# SM3320-BATT-EV.net
KiCad netlist of a schematic drawn in Altium Designer
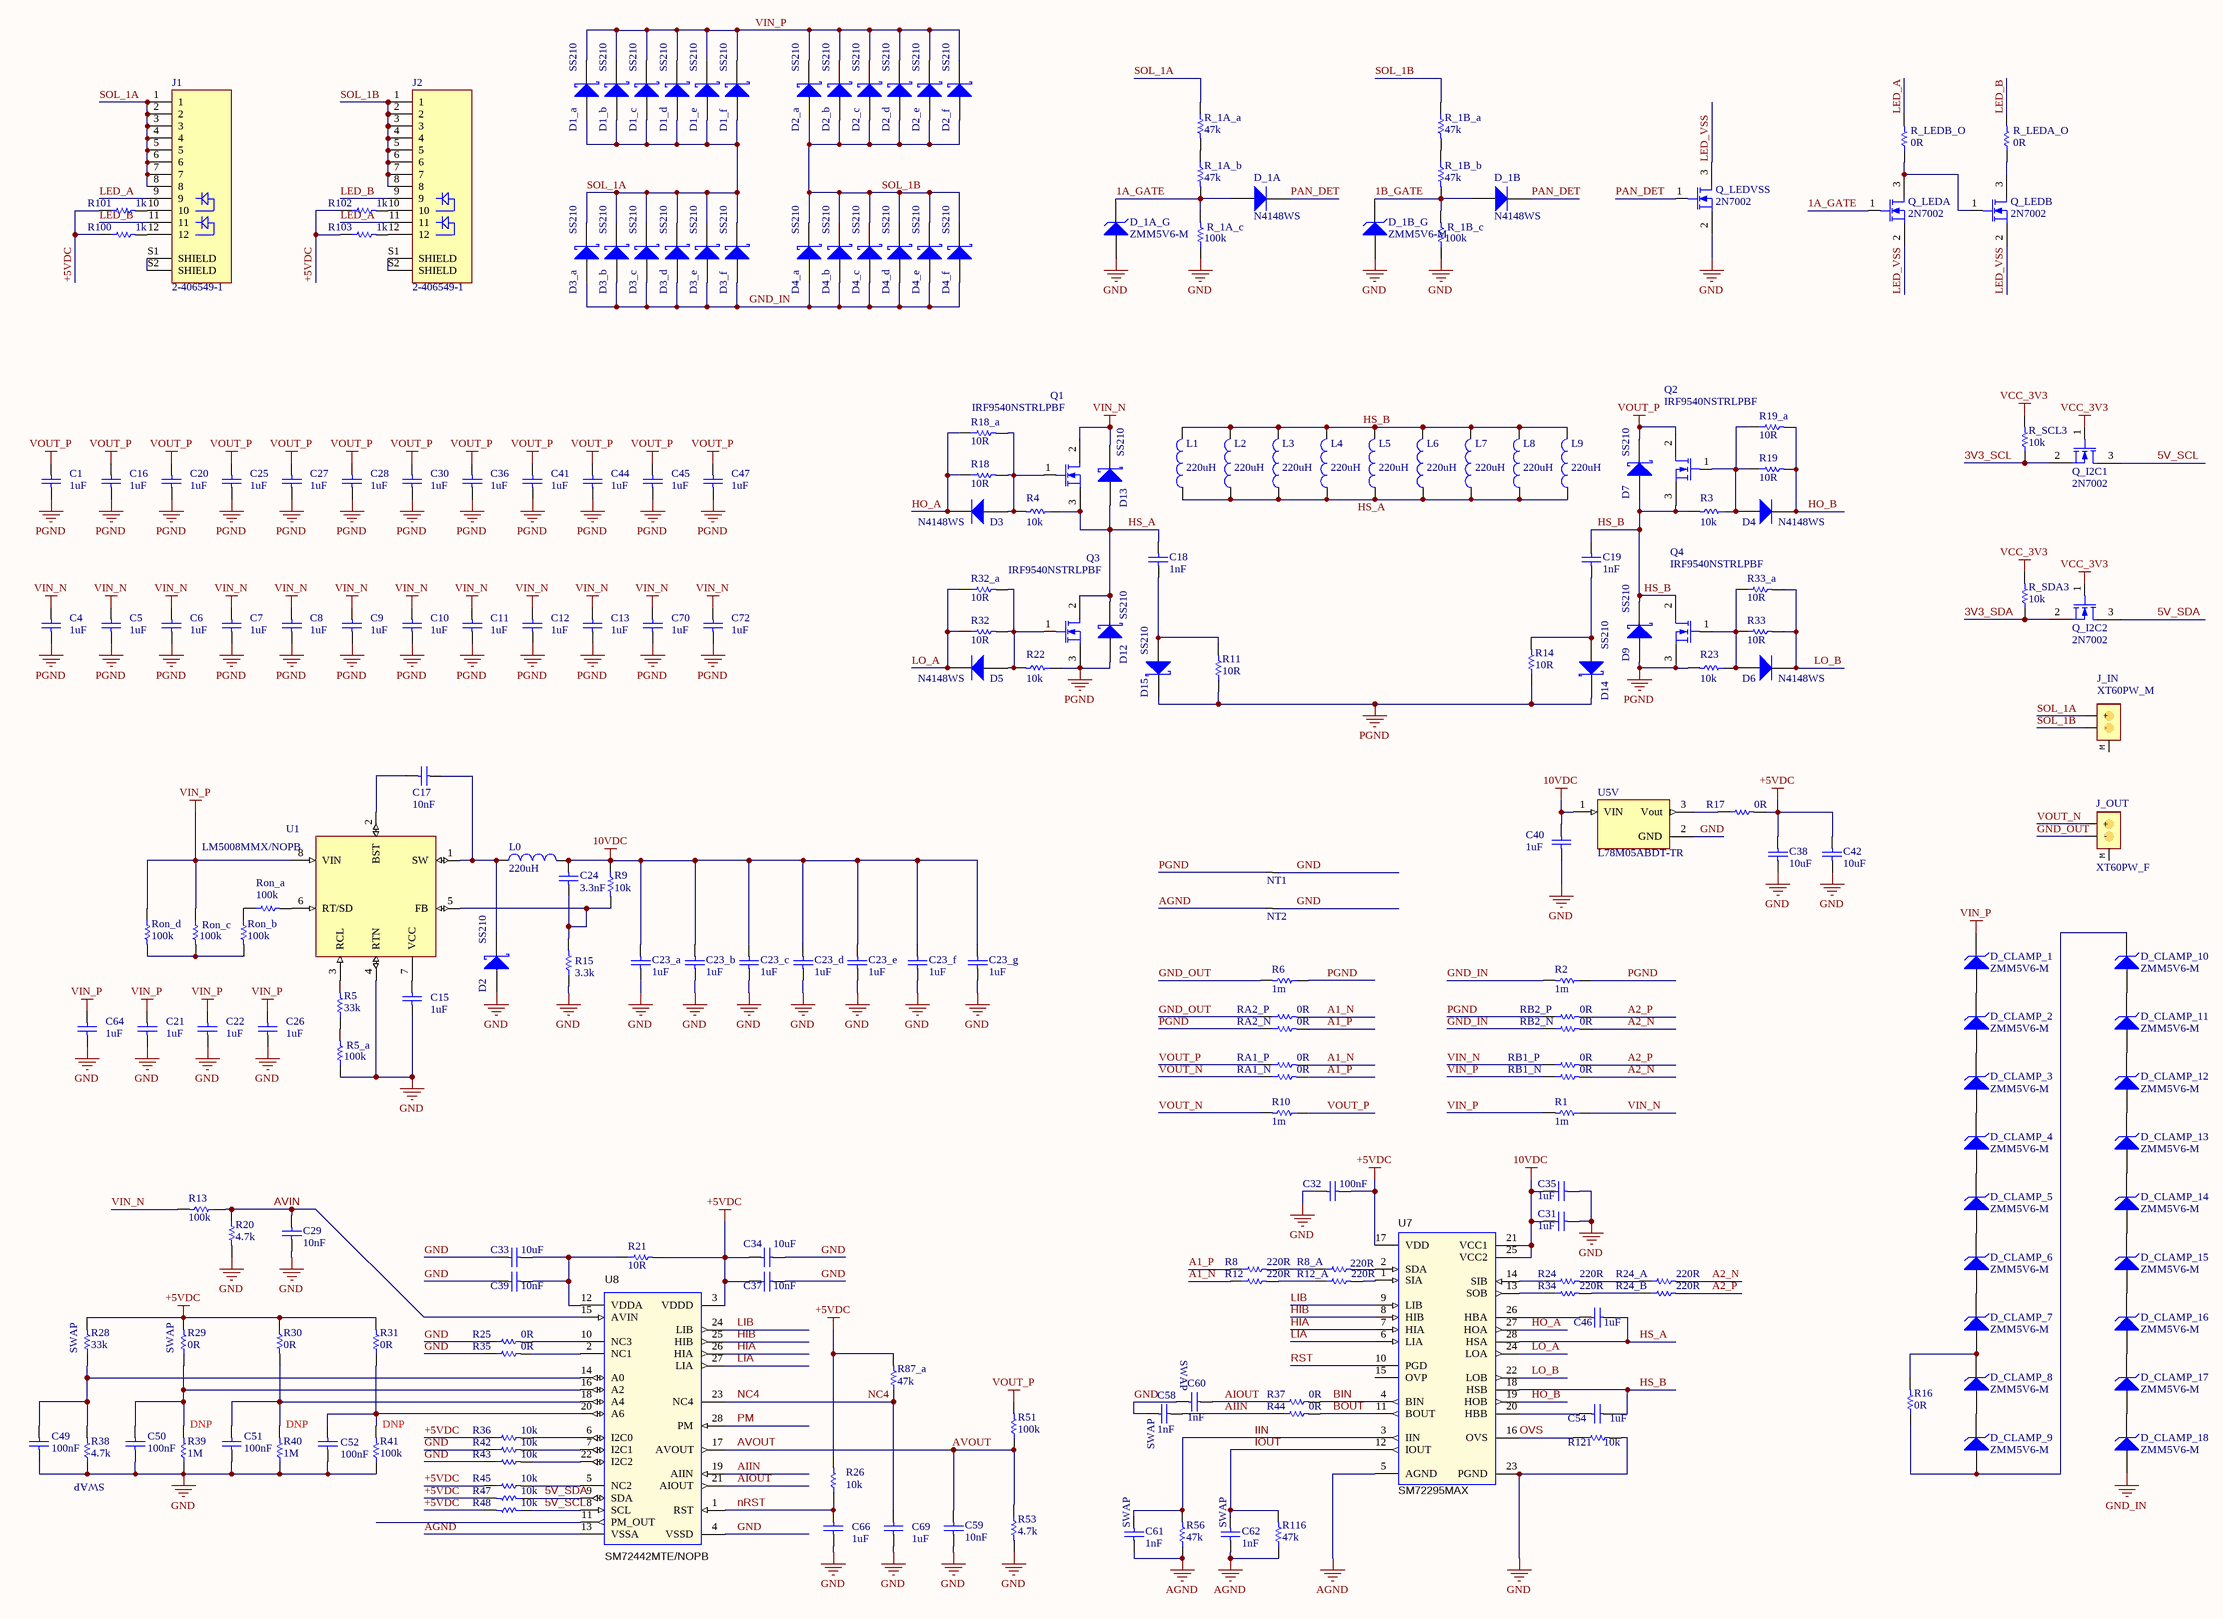
[diagram p0: SM3320-BATT-EV.SchDoc]

(export (version "E")
  (design (tool "Eeschema 10.0.6"))
  (components
    (comp (ref "C1")
      (value "1uF")
      (footprint "C_1206")
      (description "C - CAPACITOR - MLCC - 1uF - 100V - 1206 - X7R")
      (fields (field (name "LCSC PART #") "C91151") (field (name "Comment") "1206B105K101NT"))
      (libsource (lib "JLC_PCB") (part "1206B105K101NT"))
    )
    (comp (ref "C4")
      (value "1uF")
      (footprint "C_1206")
      (description "C - CAPACITOR - MLCC - 1uF - 100V - 1206 - X7R")
      (fields (field (name "LCSC PART #") "C91151") (field (name "Comment") "1206B105K101NT"))
      (libsource (lib "JLC_PCB") (part "1206B105K101NT"))
    )
    (comp (ref "C5")
      (value "1uF")
      (footprint "C_1206")
      (description "C - CAPACITOR - MLCC - 1uF - 100V - 1206 - X7R")
      (fields (field (name "LCSC PART #") "C91151") (field (name "Comment") "1206B105K101NT"))
      (libsource (lib "JLC_PCB") (part "1206B105K101NT"))
    )
    (comp (ref "C6")
      (value "1uF")
      (footprint "C_1206")
      (description "C - CAPACITOR - MLCC - 1uF - 100V - 1206 - X7R")
      (fields (field (name "LCSC PART #") "C91151") (field (name "Comment") "1206B105K101NT"))
      (libsource (lib "JLC_PCB") (part "1206B105K101NT"))
    )
    (comp (ref "C7")
      (value "1uF")
      (footprint "C_1206")
      (description "C - CAPACITOR - MLCC - 1uF - 100V - 1206 - X7R")
      (fields (field (name "LCSC PART #") "C91151") (field (name "Comment") "1206B105K101NT"))
      (libsource (lib "JLC_PCB") (part "1206B105K101NT"))
    )
    (comp (ref "C8")
      (value "1uF")
      (footprint "C_1206")
      (description "C - CAPACITOR - MLCC - 1uF - 100V - 1206 - X7R")
      (fields (field (name "LCSC PART #") "C91151") (field (name "Comment") "1206B105K101NT"))
      (libsource (lib "JLC_PCB") (part "1206B105K101NT"))
    )
    (comp (ref "C9")
      (value "1uF")
      (footprint "C_1206")
      (description "C - CAPACITOR - MLCC - 1uF - 100V - 1206 - X7R")
      (fields (field (name "LCSC PART #") "C91151") (field (name "Comment") "1206B105K101NT"))
      (libsource (lib "JLC_PCB") (part "1206B105K101NT"))
    )
    (comp (ref "C10")
      (value "1uF")
      (footprint "C_1206")
      (description "C - CAPACITOR - MLCC - 1uF - 100V - 1206 - X7R")
      (fields (field (name "LCSC PART #") "C91151") (field (name "Comment") "1206B105K101NT"))
      (libsource (lib "JLC_PCB") (part "1206B105K101NT"))
    )
    (comp (ref "C11")
      (value "1uF")
      (footprint "C_1206")
      (description "C - CAPACITOR - MLCC - 1uF - 100V - 1206 - X7R")
      (fields (field (name "LCSC PART #") "C91151") (field (name "Comment") "1206B105K101NT"))
      (libsource (lib "JLC_PCB") (part "1206B105K101NT"))
    )
    (comp (ref "C12")
      (value "1uF")
      (footprint "C_1206")
      (description "C - CAPACITOR - MLCC - 1uF - 100V - 1206 - X7R")
      (fields (field (name "LCSC PART #") "C91151") (field (name "Comment") "1206B105K101NT"))
      (libsource (lib "JLC_PCB") (part "1206B105K101NT"))
    )
    (comp (ref "C13")
      (value "1uF")
      (footprint "C_1206")
      (description "C - CAPACITOR - MLCC - 1uF - 100V - 1206 - X7R")
      (fields (field (name "LCSC PART #") "C91151") (field (name "Comment") "1206B105K101NT"))
      (libsource (lib "JLC_PCB") (part "1206B105K101NT"))
    )
    (comp (ref "C15")
      (value "1uF")
      (footprint "C_0402")
      (description "C - CAPACITOR - MLCC - 1uF - 25V - 0402")
      (fields (field (name "LCSC PART #") "C52923") (field (name "Comment") "CL05A105KA5NQNC"))
      (libsource (lib "JLC_PCB") (part "CL05A105KA5NQNC"))
    )
    (comp (ref "C16")
      (value "1uF")
      (footprint "C_1206")
      (description "C - CAPACITOR - MLCC - 1uF - 100V - 1206 - X7R")
      (fields (field (name "LCSC PART #") "C91151") (field (name "Comment") "1206B105K101NT"))
      (libsource (lib "JLC_PCB") (part "1206B105K101NT"))
    )
    (comp (ref "C17")
      (value "10nF")
      (footprint "C_0402")
      (description "C - CAPACITOR - MLCC - 10nF - 50V - 0402")
      (fields (field (name "LCSC PART #") "C15195") (field (name "Comment") "CL05B103KB5NNNC"))
      (libsource (lib "JLC_PCB") (part "CL05B103KB5NNNC"))
    )
    (comp (ref "C18")
      (value "1nF")
      (footprint "C_1206")
      (description "C - CAPACITOR - MLCC - 1nF - 2000V - 1206 - X7R")
      (fields (field (name "LCSC PART #") "C9196") (field (name "Comment") "1206B102K202NT"))
      (libsource (lib "JLC_PCB") (part "1206B102K202NT"))
    )
    (comp (ref "C19")
      (value "1nF")
      (footprint "C_1206")
      (description "C - CAPACITOR - MLCC - 1nF - 2000V - 1206 - X7R")
      (fields (field (name "LCSC PART #") "C9196") (field (name "Comment") "1206B102K202NT"))
      (libsource (lib "JLC_PCB") (part "1206B102K202NT"))
    )
    (comp (ref "C20")
      (value "1uF")
      (footprint "C_1206")
      (description "C - CAPACITOR - MLCC - 1uF - 100V - 1206 - X7R")
      (fields (field (name "LCSC PART #") "C91151") (field (name "Comment") "1206B105K101NT"))
      (libsource (lib "JLC_PCB") (part "1206B105K101NT"))
    )
    (comp (ref "C21")
      (value "1uF")
      (footprint "C_1206")
      (description "C - CAPACITOR - MLCC - 1uF - 100V - 1206 - X7R")
      (fields (field (name "LCSC PART #") "C91151") (field (name "Comment") "1206B105K101NT"))
      (libsource (lib "JLC_PCB") (part "1206B105K101NT"))
    )
    (comp (ref "C22")
      (value "1uF")
      (footprint "C_1206")
      (description "C - CAPACITOR - MLCC - 1uF - 100V - 1206 - X7R")
      (fields (field (name "LCSC PART #") "C91151") (field (name "Comment") "1206B105K101NT"))
      (libsource (lib "JLC_PCB") (part "1206B105K101NT"))
    )
    (comp (ref "C23_a")
      (value "1uF")
      (footprint "C_0402")
      (description "C - CAPACITOR - MLCC - 1uF - 25V - 0402")
      (fields (field (name "LCSC PART #") "C52923") (field (name "Comment") "CL05A105KA5NQNC"))
      (libsource (lib "JLC_PCB") (part "CL05A105KA5NQNC"))
    )
    (comp (ref "C23_b")
      (value "1uF")
      (footprint "C_0402")
      (description "C - CAPACITOR - MLCC - 1uF - 25V - 0402")
      (fields (field (name "LCSC PART #") "C52923") (field (name "Comment") "CL05A105KA5NQNC"))
      (libsource (lib "JLC_PCB") (part "CL05A105KA5NQNC"))
    )
    (comp (ref "C23_c")
      (value "1uF")
      (footprint "C_0402")
      (description "C - CAPACITOR - MLCC - 1uF - 25V - 0402")
      (fields (field (name "LCSC PART #") "C52923") (field (name "Comment") "CL05A105KA5NQNC"))
      (libsource (lib "JLC_PCB") (part "CL05A105KA5NQNC"))
    )
    (comp (ref "C23_d")
      (value "1uF")
      (footprint "C_0402")
      (description "C - CAPACITOR - MLCC - 1uF - 25V - 0402")
      (fields (field (name "LCSC PART #") "C52923") (field (name "Comment") "CL05A105KA5NQNC"))
      (libsource (lib "JLC_PCB") (part "CL05A105KA5NQNC"))
    )
    (comp (ref "C23_e")
      (value "1uF")
      (footprint "C_0402")
      (description "C - CAPACITOR - MLCC - 1uF - 25V - 0402")
      (fields (field (name "LCSC PART #") "C52923") (field (name "Comment") "CL05A105KA5NQNC"))
      (libsource (lib "JLC_PCB") (part "CL05A105KA5NQNC"))
    )
    (comp (ref "C23_f")
      (value "1uF")
      (footprint "C_0402")
      (description "C - CAPACITOR - MLCC - 1uF - 25V - 0402")
      (fields (field (name "LCSC PART #") "C52923") (field (name "Comment") "CL05A105KA5NQNC"))
      (libsource (lib "JLC_PCB") (part "CL05A105KA5NQNC"))
    )
    (comp (ref "C23_g")
      (value "1uF")
      (footprint "C_0402")
      (description "C - CAPACITOR - MLCC - 1uF - 25V - 0402")
      (fields (field (name "LCSC PART #") "C52923") (field (name "Comment") "CL05A105KA5NQNC"))
      (libsource (lib "JLC_PCB") (part "CL05A105KA5NQNC"))
    )
    (comp (ref "C24")
      (value "3.3nF")
      (footprint "C_0402")
      (description "C - CAPACITOR - MLCC - 3.3nF - 50V - 0402")
      (fields (field (name "LCSC PART #") "C26404") (field (name "Comment") "CL05B332KB5NNNC"))
      (libsource (lib "JLC_PCB") (part "CL05B332KB5NNNC"))
    )
    (comp (ref "C25")
      (value "1uF")
      (footprint "C_1206")
      (description "C - CAPACITOR - MLCC - 1uF - 100V - 1206 - X7R")
      (fields (field (name "LCSC PART #") "C91151") (field (name "Comment") "1206B105K101NT"))
      (libsource (lib "JLC_PCB") (part "1206B105K101NT"))
    )
    (comp (ref "C26")
      (value "1uF")
      (footprint "C_1206")
      (description "C - CAPACITOR - MLCC - 1uF - 100V - 1206 - X7R")
      (fields (field (name "LCSC PART #") "C91151") (field (name "Comment") "1206B105K101NT"))
      (libsource (lib "JLC_PCB") (part "1206B105K101NT"))
    )
    (comp (ref "C27")
      (value "1uF")
      (footprint "C_1206")
      (description "C - CAPACITOR - MLCC - 1uF - 100V - 1206 - X7R")
      (fields (field (name "LCSC PART #") "C91151") (field (name "Comment") "1206B105K101NT"))
      (libsource (lib "JLC_PCB") (part "1206B105K101NT"))
    )
    (comp (ref "C28")
      (value "1uF")
      (footprint "C_1206")
      (description "C - CAPACITOR - MLCC - 1uF - 100V - 1206 - X7R")
      (fields (field (name "LCSC PART #") "C91151") (field (name "Comment") "1206B105K101NT"))
      (libsource (lib "JLC_PCB") (part "1206B105K101NT"))
    )
    (comp (ref "C29")
      (value "10nF")
      (footprint "C_0402")
      (description "C - CAPACITOR - MLCC - 10nF - 50V - 0402")
      (fields (field (name "LCSC PART #") "C15195") (field (name "Comment") "CL05B103KB5NNNC"))
      (libsource (lib "JLC_PCB") (part "CL05B103KB5NNNC"))
    )
    (comp (ref "C30")
      (value "1uF")
      (footprint "C_1206")
      (description "C - CAPACITOR - MLCC - 1uF - 100V - 1206 - X7R")
      (fields (field (name "LCSC PART #") "C91151") (field (name "Comment") "1206B105K101NT"))
      (libsource (lib "JLC_PCB") (part "1206B105K101NT"))
    )
    (comp (ref "C31")
      (value "1uF")
      (footprint "C_0402")
      (description "C - CAPACITOR - MLCC - 1uF - 25V - 0402")
      (fields (field (name "LCSC PART #") "C52923") (field (name "Comment") "CL05A105KA5NQNC"))
      (libsource (lib "JLC_PCB") (part "CL05A105KA5NQNC"))
    )
    (comp (ref "C32")
      (value "100nF")
      (footprint "C_0402")
      (description "C - CAPACITOR - MLCC - 100nF - 16V - 0402")
      (fields (field (name "LCSC PART #") "C1525") (field (name "Comment") "CL05B104KO5NNNC"))
      (libsource (lib "JLC_PCB") (part "CL05B104KO5NNNC"))
    )
    (comp (ref "C33")
      (value "10uF")
      (footprint "C_0402")
      (description "C - CAPACITOR - MLCC - 10uF - 6.3V - 0402")
      (fields (field (name "LCSC PART #") "C15525") (field (name "Comment") "CL05A106MQ5NUNC"))
      (libsource (lib "JLC_PCB") (part "CL05A106MQ5NUNC"))
    )
    (comp (ref "C34")
      (value "10uF")
      (footprint "C_0402")
      (description "C - CAPACITOR - MLCC - 10uF - 6.3V - 0402")
      (fields (field (name "LCSC PART #") "C15525") (field (name "Comment") "CL05A106MQ5NUNC"))
      (libsource (lib "JLC_PCB") (part "CL05A106MQ5NUNC"))
    )
    (comp (ref "C35")
      (value "1uF")
      (footprint "C_0402")
      (description "C - CAPACITOR - MLCC - 1uF - 25V - 0402")
      (fields (field (name "LCSC PART #") "C52923") (field (name "Comment") "CL05A105KA5NQNC"))
      (libsource (lib "JLC_PCB") (part "CL05A105KA5NQNC"))
    )
    (comp (ref "C36")
      (value "1uF")
      (footprint "C_1206")
      (description "C - CAPACITOR - MLCC - 1uF - 100V - 1206 - X7R")
      (fields (field (name "LCSC PART #") "C91151") (field (name "Comment") "1206B105K101NT"))
      (libsource (lib "JLC_PCB") (part "1206B105K101NT"))
    )
    (comp (ref "C37")
      (value "10nF")
      (footprint "C_0402")
      (description "C - CAPACITOR - MLCC - 10nF - 50V - 0402")
      (fields (field (name "LCSC PART #") "C15195") (field (name "Comment") "CL05B103KB5NNNC"))
      (libsource (lib "JLC_PCB") (part "CL05B103KB5NNNC"))
    )
    (comp (ref "C38")
      (value "10uF")
      (footprint "C_0402")
      (description "C - CAPACITOR - MLCC - 10uF - 6.3V - 0402")
      (fields (field (name "LCSC PART #") "C15525") (field (name "Comment") "CL05A106MQ5NUNC"))
      (libsource (lib "JLC_PCB") (part "CL05A106MQ5NUNC"))
    )
    (comp (ref "C39")
      (value "10nF")
      (footprint "C_0402")
      (description "C - CAPACITOR - MLCC - 10nF - 50V - 0402")
      (fields (field (name "LCSC PART #") "C15195") (field (name "Comment") "CL05B103KB5NNNC"))
      (libsource (lib "JLC_PCB") (part "CL05B103KB5NNNC"))
    )
    (comp (ref "C40")
      (value "1uF")
      (footprint "C_0402")
      (description "C - CAPACITOR - MLCC - 1uF - 25V - 0402")
      (fields (field (name "LCSC PART #") "C52923") (field (name "Comment") "CL05A105KA5NQNC"))
      (libsource (lib "JLC_PCB") (part "CL05A105KA5NQNC"))
    )
    (comp (ref "C41")
      (value "1uF")
      (footprint "C_1206")
      (description "C - CAPACITOR - MLCC - 1uF - 100V - 1206 - X7R")
      (fields (field (name "LCSC PART #") "C91151") (field (name "Comment") "1206B105K101NT"))
      (libsource (lib "JLC_PCB") (part "1206B105K101NT"))
    )
    (comp (ref "C42")
      (value "10uF")
      (footprint "C_0402")
      (description "C - CAPACITOR - MLCC - 10uF - 6.3V - 0402")
      (fields (field (name "LCSC PART #") "C15525") (field (name "Comment") "CL05A106MQ5NUNC"))
      (libsource (lib "JLC_PCB") (part "CL05A106MQ5NUNC"))
    )
    (comp (ref "C44")
      (value "1uF")
      (footprint "C_1206")
      (description "C - CAPACITOR - MLCC - 1uF - 100V - 1206 - X7R")
      (fields (field (name "LCSC PART #") "C91151") (field (name "Comment") "1206B105K101NT"))
      (libsource (lib "JLC_PCB") (part "1206B105K101NT"))
    )
    (comp (ref "C45")
      (value "1uF")
      (footprint "C_1206")
      (description "C - CAPACITOR - MLCC - 1uF - 100V - 1206 - X7R")
      (fields (field (name "LCSC PART #") "C91151") (field (name "Comment") "1206B105K101NT"))
      (libsource (lib "JLC_PCB") (part "1206B105K101NT"))
    )
    (comp (ref "C46")
      (value "1uF")
      (footprint "C_0402")
      (description "C - CAPACITOR - MLCC - 1uF - 25V - 0402")
      (fields (field (name "LCSC PART #") "C52923") (field (name "Comment") "CL05A105KA5NQNC"))
      (libsource (lib "JLC_PCB") (part "CL05A105KA5NQNC"))
    )
    (comp (ref "C47")
      (value "1uF")
      (footprint "C_1206")
      (description "C - CAPACITOR - MLCC - 1uF - 100V - 1206 - X7R")
      (fields (field (name "LCSC PART #") "C91151") (field (name "Comment") "1206B105K101NT"))
      (libsource (lib "JLC_PCB") (part "1206B105K101NT"))
    )
    (comp (ref "C49")
      (value "100nF")
      (footprint "C_0402")
      (description "C - CAPACITOR - MLCC - 100nF - 16V - 0402")
      (fields (field (name "LCSC PART #") "C1525") (field (name "Comment") "CL05B104KO5NNNC"))
      (libsource (lib "JLC_PCB") (part "CL05B104KO5NNNC"))
    )
    (comp (ref "C50")
      (value "100nF")
      (footprint "C_0402")
      (description "C - CAPACITOR - MLCC - 100nF - 16V - 0402")
      (fields (field (name "LCSC PART #") "C1525") (field (name "Comment") "CL05B104KO5NNNC"))
      (libsource (lib "JLC_PCB") (part "CL05B104KO5NNNC"))
    )
    (comp (ref "C51")
      (value "100nF")
      (footprint "C_0402")
      (description "C - CAPACITOR - MLCC - 100nF - 16V - 0402")
      (fields (field (name "LCSC PART #") "C1525") (field (name "Comment") "CL05B104KO5NNNC"))
      (libsource (lib "JLC_PCB") (part "CL05B104KO5NNNC"))
    )
    (comp (ref "C52")
      (value "100nF")
      (footprint "C_0402")
      (description "C - CAPACITOR - MLCC - 100nF - 16V - 0402")
      (fields (field (name "LCSC PART #") "C1525") (field (name "Comment") "CL05B104KO5NNNC"))
      (libsource (lib "JLC_PCB") (part "CL05B104KO5NNNC"))
    )
    (comp (ref "C54")
      (value "1uF")
      (footprint "C_0402")
      (description "C - CAPACITOR - MLCC - 1uF - 25V - 0402")
      (fields (field (name "LCSC PART #") "C52923") (field (name "Comment") "CL05A105KA5NQNC"))
      (libsource (lib "JLC_PCB") (part "CL05A105KA5NQNC"))
    )
    (comp (ref "C58")
      (value "1nF")
      (footprint "C_0402")
      (description "C - CAPACITOR - MLCC - 1nF - 50V - 0402")
      (fields (field (name "LCSC PART #") "C1523") (field (name "Comment") "0402B102K500NT"))
      (libsource (lib "JLC_PCB") (part "0402B102K500NT"))
    )
    (comp (ref "C59")
      (value "10nF")
      (footprint "C_0402")
      (description "C - CAPACITOR - MLCC - 10nF - 50V - 0402")
      (fields (field (name "LCSC PART #") "C15195") (field (name "Comment") "CL05B103KB5NNNC"))
      (libsource (lib "JLC_PCB") (part "CL05B103KB5NNNC"))
    )
    (comp (ref "C60")
      (value "1nF")
      (footprint "C_0402")
      (description "C - CAPACITOR - MLCC - 1nF - 50V - 0402")
      (fields (field (name "LCSC PART #") "C1523") (field (name "Comment") "0402B102K500NT"))
      (libsource (lib "JLC_PCB") (part "0402B102K500NT"))
    )
    (comp (ref "C61")
      (value "1nF")
      (footprint "C_0402")
      (description "C - CAPACITOR - MLCC - 1nF - 50V - 0402")
      (fields (field (name "LCSC PART #") "C1523") (field (name "Comment") "0402B102K500NT"))
      (libsource (lib "JLC_PCB") (part "0402B102K500NT"))
    )
    (comp (ref "C62")
      (value "1nF")
      (footprint "C_0402")
      (description "C - CAPACITOR - MLCC - 1nF - 50V - 0402")
      (fields (field (name "LCSC PART #") "C1523") (field (name "Comment") "0402B102K500NT"))
      (libsource (lib "JLC_PCB") (part "0402B102K500NT"))
    )
    (comp (ref "C64")
      (value "1uF")
      (footprint "C_1206")
      (description "C - CAPACITOR - MLCC - 1uF - 100V - 1206 - X7R")
      (fields (field (name "LCSC PART #") "C91151") (field (name "Comment") "1206B105K101NT"))
      (libsource (lib "JLC_PCB") (part "1206B105K101NT"))
    )
    (comp (ref "C66")
      (value "1uF")
      (footprint "C_0402")
      (description "C - CAPACITOR - MLCC - 1uF - 25V - 0402")
      (fields (field (name "LCSC PART #") "C52923") (field (name "Comment") "CL05A105KA5NQNC"))
      (libsource (lib "JLC_PCB") (part "CL05A105KA5NQNC"))
    )
    (comp (ref "C69")
      (value "1uF")
      (footprint "C_0402")
      (description "C - CAPACITOR - MLCC - 1uF - 25V - 0402")
      (fields (field (name "LCSC PART #") "C52923") (field (name "Comment") "CL05A105KA5NQNC"))
      (libsource (lib "JLC_PCB") (part "CL05A105KA5NQNC"))
    )
    (comp (ref "C70")
      (value "1uF")
      (footprint "C_1206")
      (description "C - CAPACITOR - MLCC - 1uF - 100V - 1206 - X7R")
      (fields (field (name "LCSC PART #") "C91151") (field (name "Comment") "1206B105K101NT"))
      (libsource (lib "JLC_PCB") (part "1206B105K101NT"))
    )
    (comp (ref "C72")
      (value "1uF")
      (footprint "C_1206")
      (description "C - CAPACITOR - MLCC - 1uF - 100V - 1206 - X7R")
      (fields (field (name "LCSC PART #") "C91151") (field (name "Comment") "1206B105K101NT"))
      (libsource (lib "JLC_PCB") (part "1206B105K101NT"))
    )
    (comp (ref "D1_a")
      (value "SS210")
      (footprint "DO-214AC")
      (description "D - DIODE - SCHOTTKY - 100V - 2A")
      (fields (field (name "LCSC PART #") "C14996"))
      (libsource (lib "JLC_PCB") (part "SS210"))
    )
    (comp (ref "D1_b")
      (value "SS210")
      (footprint "DO-214AC")
      (description "D - DIODE - SCHOTTKY - 100V - 2A")
      (fields (field (name "LCSC PART #") "C14996"))
      (libsource (lib "JLC_PCB") (part "SS210"))
    )
    (comp (ref "D1_c")
      (value "SS210")
      (footprint "DO-214AC")
      (description "D - DIODE - SCHOTTKY - 100V - 2A")
      (fields (field (name "LCSC PART #") "C14996"))
      (libsource (lib "JLC_PCB") (part "SS210"))
    )
    (comp (ref "D1_d")
      (value "SS210")
      (footprint "DO-214AC")
      (description "D - DIODE - SCHOTTKY - 100V - 2A")
      (fields (field (name "LCSC PART #") "C14996"))
      (libsource (lib "JLC_PCB") (part "SS210"))
    )
    (comp (ref "D1_e")
      (value "SS210")
      (footprint "DO-214AC")
      (description "D - DIODE - SCHOTTKY - 100V - 2A")
      (fields (field (name "LCSC PART #") "C14996"))
      (libsource (lib "JLC_PCB") (part "SS210"))
    )
    (comp (ref "D1_f")
      (value "SS210")
      (footprint "DO-214AC")
      (description "D - DIODE - SCHOTTKY - 100V - 2A")
      (fields (field (name "LCSC PART #") "C14996"))
      (libsource (lib "JLC_PCB") (part "SS210"))
    )
    (comp (ref "D2")
      (value "SS210")
      (footprint "DO-214AC")
      (description "D - DIODE - SCHOTTKY - 100V - 2A")
      (fields (field (name "LCSC PART #") "C14996"))
      (libsource (lib "JLC_PCB") (part "SS210"))
    )
    (comp (ref "D2_a")
      (value "SS210")
      (footprint "DO-214AC")
      (description "D - DIODE - SCHOTTKY - 100V - 2A")
      (fields (field (name "LCSC PART #") "C14996"))
      (libsource (lib "JLC_PCB") (part "SS210"))
    )
    (comp (ref "D2_b")
      (value "SS210")
      (footprint "DO-214AC")
      (description "D - DIODE - SCHOTTKY - 100V - 2A")
      (fields (field (name "LCSC PART #") "C14996"))
      (libsource (lib "JLC_PCB") (part "SS210"))
    )
    (comp (ref "D2_c")
      (value "SS210")
      (footprint "DO-214AC")
      (description "D - DIODE - SCHOTTKY - 100V - 2A")
      (fields (field (name "LCSC PART #") "C14996"))
      (libsource (lib "JLC_PCB") (part "SS210"))
    )
    (comp (ref "D2_d")
      (value "SS210")
      (footprint "DO-214AC")
      (description "D - DIODE - SCHOTTKY - 100V - 2A")
      (fields (field (name "LCSC PART #") "C14996"))
      (libsource (lib "JLC_PCB") (part "SS210"))
    )
    (comp (ref "D2_e")
      (value "SS210")
      (footprint "DO-214AC")
      (description "D - DIODE - SCHOTTKY - 100V - 2A")
      (fields (field (name "LCSC PART #") "C14996"))
      (libsource (lib "JLC_PCB") (part "SS210"))
    )
    (comp (ref "D2_f")
      (value "SS210")
      (footprint "DO-214AC")
      (description "D - DIODE - SCHOTTKY - 100V - 2A")
      (fields (field (name "LCSC PART #") "C14996"))
      (libsource (lib "JLC_PCB") (part "SS210"))
    )
    (comp (ref "D3")
      (value "N4148WS")
      (footprint "SOD-323")
      (description "D - DIODE - FAST TRR - 100V - 150mA - 4ns")
      (fields (field (name "LCSC PART #") "C2128"))
      (libsource (lib "JLC_PCB") (part "N4148WS"))
    )
    (comp (ref "D3_a")
      (value "SS210")
      (footprint "DO-214AC")
      (description "D - DIODE - SCHOTTKY - 100V - 2A")
      (fields (field (name "LCSC PART #") "C14996"))
      (libsource (lib "JLC_PCB") (part "SS210"))
    )
    (comp (ref "D3_b")
      (value "SS210")
      (footprint "DO-214AC")
      (description "D - DIODE - SCHOTTKY - 100V - 2A")
      (fields (field (name "LCSC PART #") "C14996"))
      (libsource (lib "JLC_PCB") (part "SS210"))
    )
    (comp (ref "D3_c")
      (value "SS210")
      (footprint "DO-214AC")
      (description "D - DIODE - SCHOTTKY - 100V - 2A")
      (fields (field (name "LCSC PART #") "C14996"))
      (libsource (lib "JLC_PCB") (part "SS210"))
    )
    (comp (ref "D3_d")
      (value "SS210")
      (footprint "DO-214AC")
      (description "D - DIODE - SCHOTTKY - 100V - 2A")
      (fields (field (name "LCSC PART #") "C14996"))
      (libsource (lib "JLC_PCB") (part "SS210"))
    )
    (comp (ref "D3_e")
      (value "SS210")
      (footprint "DO-214AC")
      (description "D - DIODE - SCHOTTKY - 100V - 2A")
      (fields (field (name "LCSC PART #") "C14996"))
      (libsource (lib "JLC_PCB") (part "SS210"))
    )
    (comp (ref "D3_f")
      (value "SS210")
      (footprint "DO-214AC")
      (description "D - DIODE - SCHOTTKY - 100V - 2A")
      (fields (field (name "LCSC PART #") "C14996"))
      (libsource (lib "JLC_PCB") (part "SS210"))
    )
    (comp (ref "D4")
      (value "N4148WS")
      (footprint "SOD-323")
      (description "D - DIODE - FAST TRR - 100V - 150mA - 4ns")
      (fields (field (name "LCSC PART #") "C2128"))
      (libsource (lib "JLC_PCB") (part "N4148WS"))
    )
    (comp (ref "D4_a")
      (value "SS210")
      (footprint "DO-214AC")
      (description "D - DIODE - SCHOTTKY - 100V - 2A")
      (fields (field (name "LCSC PART #") "C14996"))
      (libsource (lib "JLC_PCB") (part "SS210"))
    )
    (comp (ref "D4_b")
      (value "SS210")
      (footprint "DO-214AC")
      (description "D - DIODE - SCHOTTKY - 100V - 2A")
      (fields (field (name "LCSC PART #") "C14996"))
      (libsource (lib "JLC_PCB") (part "SS210"))
    )
    (comp (ref "D4_c")
      (value "SS210")
      (footprint "DO-214AC")
      (description "D - DIODE - SCHOTTKY - 100V - 2A")
      (fields (field (name "LCSC PART #") "C14996"))
      (libsource (lib "JLC_PCB") (part "SS210"))
    )
    (comp (ref "D4_d")
      (value "SS210")
      (footprint "DO-214AC")
      (description "D - DIODE - SCHOTTKY - 100V - 2A")
      (fields (field (name "LCSC PART #") "C14996"))
      (libsource (lib "JLC_PCB") (part "SS210"))
    )
    (comp (ref "D4_e")
      (value "SS210")
      (footprint "DO-214AC")
      (description "D - DIODE - SCHOTTKY - 100V - 2A")
      (fields (field (name "LCSC PART #") "C14996"))
      (libsource (lib "JLC_PCB") (part "SS210"))
    )
    (comp (ref "D4_f")
      (value "SS210")
      (footprint "DO-214AC")
      (description "D - DIODE - SCHOTTKY - 100V - 2A")
      (fields (field (name "LCSC PART #") "C14996"))
      (libsource (lib "JLC_PCB") (part "SS210"))
    )
    (comp (ref "D5")
      (value "N4148WS")
      (footprint "SOD-323")
      (description "D - DIODE - FAST TRR - 100V - 150mA - 4ns")
      (fields (field (name "LCSC PART #") "C2128"))
      (libsource (lib "JLC_PCB") (part "N4148WS"))
    )
    (comp (ref "D6")
      (value "N4148WS")
      (footprint "SOD-323")
      (description "D - DIODE - FAST TRR - 100V - 150mA - 4ns")
      (fields (field (name "LCSC PART #") "C2128"))
      (libsource (lib "JLC_PCB") (part "N4148WS"))
    )
    (comp (ref "D7")
      (value "SS210")
      (footprint "DO-214AC")
      (description "D - DIODE - SCHOTTKY - 100V - 2A")
      (fields (field (name "LCSC PART #") "C14996"))
      (libsource (lib "JLC_PCB") (part "SS210"))
    )
    (comp (ref "D9")
      (value "SS210")
      (footprint "DO-214AC")
      (description "D - DIODE - SCHOTTKY - 100V - 2A")
      (fields (field (name "LCSC PART #") "C14996"))
      (libsource (lib "JLC_PCB") (part "SS210"))
    )
    (comp (ref "D12")
      (value "SS210")
      (footprint "DO-214AC")
      (description "D - DIODE - SCHOTTKY - 100V - 2A")
      (fields (field (name "LCSC PART #") "C14996"))
      (libsource (lib "JLC_PCB") (part "SS210"))
    )
    (comp (ref "D13")
      (value "SS210")
      (footprint "DO-214AC")
      (description "D - DIODE - SCHOTTKY - 100V - 2A")
      (fields (field (name "LCSC PART #") "C14996"))
      (libsource (lib "JLC_PCB") (part "SS210"))
    )
    (comp (ref "D14")
      (value "SS210")
      (footprint "DO-214AC")
      (description "D - DIODE - SCHOTTKY - 100V - 2A")
      (fields (field (name "LCSC PART #") "C14996"))
      (libsource (lib "JLC_PCB") (part "SS210"))
    )
    (comp (ref "D15")
      (value "SS210")
      (footprint "DO-214AC")
      (description "D - DIODE - SCHOTTKY - 100V - 2A")
      (fields (field (name "LCSC PART #") "C14996"))
      (libsource (lib "JLC_PCB") (part "SS210"))
    )
    (comp (ref "D_1A")
      (value "N4148WS")
      (footprint "SOD-323")
      (description "D - DIODE - FAST TRR - 100V - 150mA - 4ns")
      (fields (field (name "LCSC PART #") "C2128"))
      (libsource (lib "JLC_PCB") (part "N4148WS"))
    )
    (comp (ref "D_1A_G")
      (value "ZMM5V6-M")
      (footprint "DO-213AA")
      (description "D - DIODE - ZENER - 5.6V - 500mW")
      (fields (field (name "LCSC PART #") "C8062"))
      (libsource (lib "JLC_PCB") (part "ZMM5V6-M"))
    )
    (comp (ref "D_1B")
      (value "N4148WS")
      (footprint "SOD-323")
      (description "D - DIODE - FAST TRR - 100V - 150mA - 4ns")
      (fields (field (name "LCSC PART #") "C2128"))
      (libsource (lib "JLC_PCB") (part "N4148WS"))
    )
    (comp (ref "D_1B_G")
      (value "ZMM5V6-M")
      (footprint "DO-213AA")
      (description "D - DIODE - ZENER - 5.6V - 500mW")
      (fields (field (name "LCSC PART #") "C8062"))
      (libsource (lib "JLC_PCB") (part "ZMM5V6-M"))
    )
    (comp (ref "D_CLAMP_1")
      (value "ZMM5V6-M")
      (footprint "DO-213AA")
      (description "D - DIODE - ZENER - 5.6V - 500mW")
      (fields (field (name "LCSC PART #") "C8062"))
      (libsource (lib "JLC_PCB") (part "ZMM5V6-M"))
    )
    (comp (ref "D_CLAMP_2")
      (value "ZMM5V6-M")
      (footprint "DO-213AA")
      (description "D - DIODE - ZENER - 5.6V - 500mW")
      (fields (field (name "LCSC PART #") "C8062"))
      (libsource (lib "JLC_PCB") (part "ZMM5V6-M"))
    )
    (comp (ref "D_CLAMP_3")
      (value "ZMM5V6-M")
      (footprint "DO-213AA")
      (description "D - DIODE - ZENER - 5.6V - 500mW")
      (fields (field (name "LCSC PART #") "C8062"))
      (libsource (lib "JLC_PCB") (part "ZMM5V6-M"))
    )
    (comp (ref "D_CLAMP_4")
      (value "ZMM5V6-M")
      (footprint "DO-213AA")
      (description "D - DIODE - ZENER - 5.6V - 500mW")
      (fields (field (name "LCSC PART #") "C8062"))
      (libsource (lib "JLC_PCB") (part "ZMM5V6-M"))
    )
    (comp (ref "D_CLAMP_5")
      (value "ZMM5V6-M")
      (footprint "DO-213AA")
      (description "D - DIODE - ZENER - 5.6V - 500mW")
      (fields (field (name "LCSC PART #") "C8062"))
      (libsource (lib "JLC_PCB") (part "ZMM5V6-M"))
    )
    (comp (ref "D_CLAMP_6")
      (value "ZMM5V6-M")
      (footprint "DO-213AA")
      (description "D - DIODE - ZENER - 5.6V - 500mW")
      (fields (field (name "LCSC PART #") "C8062"))
      (libsource (lib "JLC_PCB") (part "ZMM5V6-M"))
    )
    (comp (ref "D_CLAMP_7")
      (value "ZMM5V6-M")
      (footprint "DO-213AA")
      (description "D - DIODE - ZENER - 5.6V - 500mW")
      (fields (field (name "LCSC PART #") "C8062"))
      (libsource (lib "JLC_PCB") (part "ZMM5V6-M"))
    )
    (comp (ref "D_CLAMP_8")
      (value "ZMM5V6-M")
      (footprint "DO-213AA")
      (description "D - DIODE - ZENER - 5.6V - 500mW")
      (fields (field (name "LCSC PART #") "C8062"))
      (libsource (lib "JLC_PCB") (part "ZMM5V6-M"))
    )
    (comp (ref "D_CLAMP_9")
      (value "ZMM5V6-M")
      (footprint "DO-213AA")
      (description "D - DIODE - ZENER - 5.6V - 500mW")
      (fields (field (name "LCSC PART #") "C8062"))
      (libsource (lib "JLC_PCB") (part "ZMM5V6-M"))
    )
    (comp (ref "D_CLAMP_10")
      (value "ZMM5V6-M")
      (footprint "DO-213AA")
      (description "D - DIODE - ZENER - 5.6V - 500mW")
      (fields (field (name "LCSC PART #") "C8062"))
      (libsource (lib "JLC_PCB") (part "ZMM5V6-M"))
    )
    (comp (ref "D_CLAMP_11")
      (value "ZMM5V6-M")
      (footprint "DO-213AA")
      (description "D - DIODE - ZENER - 5.6V - 500mW")
      (fields (field (name "LCSC PART #") "C8062"))
      (libsource (lib "JLC_PCB") (part "ZMM5V6-M"))
    )
    (comp (ref "D_CLAMP_12")
      (value "ZMM5V6-M")
      (footprint "DO-213AA")
      (description "D - DIODE - ZENER - 5.6V - 500mW")
      (fields (field (name "LCSC PART #") "C8062"))
      (libsource (lib "JLC_PCB") (part "ZMM5V6-M"))
    )
    (comp (ref "D_CLAMP_13")
      (value "ZMM5V6-M")
      (footprint "DO-213AA")
      (description "D - DIODE - ZENER - 5.6V - 500mW")
      (fields (field (name "LCSC PART #") "C8062"))
      (libsource (lib "JLC_PCB") (part "ZMM5V6-M"))
    )
    (comp (ref "D_CLAMP_14")
      (value "ZMM5V6-M")
      (footprint "DO-213AA")
      (description "D - DIODE - ZENER - 5.6V - 500mW")
      (fields (field (name "LCSC PART #") "C8062"))
      (libsource (lib "JLC_PCB") (part "ZMM5V6-M"))
    )
    (comp (ref "D_CLAMP_15")
      (value "ZMM5V6-M")
      (footprint "DO-213AA")
      (description "D - DIODE - ZENER - 5.6V - 500mW")
      (fields (field (name "LCSC PART #") "C8062"))
      (libsource (lib "JLC_PCB") (part "ZMM5V6-M"))
    )
    (comp (ref "D_CLAMP_16")
      (value "ZMM5V6-M")
      (footprint "DO-213AA")
      (description "D - DIODE - ZENER - 5.6V - 500mW")
      (fields (field (name "LCSC PART #") "C8062"))
      (libsource (lib "JLC_PCB") (part "ZMM5V6-M"))
    )
    (comp (ref "D_CLAMP_17")
      (value "ZMM5V6-M")
      (footprint "DO-213AA")
      (description "D - DIODE - ZENER - 5.6V - 500mW")
      (fields (field (name "LCSC PART #") "C8062"))
      (libsource (lib "JLC_PCB") (part "ZMM5V6-M"))
    )
    (comp (ref "D_CLAMP_18")
      (value "ZMM5V6-M")
      (footprint "DO-213AA")
      (description "D - DIODE - ZENER - 5.6V - 500mW")
      (fields (field (name "LCSC PART #") "C8062"))
      (libsource (lib "JLC_PCB") (part "ZMM5V6-M"))
    )
    (comp (ref "J1")
      (value "2-406549-1")
      (footprint "TE_2-406549-1")
      (description "J - JACK - ETHERNET - Right - THT")
      (fields (field (name "LCSC PART #") "C125068"))
      (libsource (lib "JLC_PCB") (part "2-406549-1"))
    )
    (comp (ref "J2")
      (value "2-406549-1")
      (footprint "TE_2-406549-1")
      (description "J - JACK - ETHERNET - Right - THT")
      (fields (field (name "LCSC PART #") "C125068"))
      (libsource (lib "JLC_PCB") (part "2-406549-1"))
    )
    (comp (ref "J_IN")
      (value "XT60PW_M")
      (footprint "XT60PW_M")
      (description "J - JACK - POWER - XT60 - RIGHT - MALE")
      (fields (field (name "LCSC PART #") "X"))
      (libsource (lib "JLC_PCB") (part "XT60PW_M"))
    )
    (comp (ref "J_OUT")
      (value "XT60PW_F")
      (footprint "XT60PW_F")
      (description "J - JACK - POWER - XT60 - RIGHT - FEMALE")
      (fields (field (name "LCSC PART #") "X"))
      (libsource (lib "JLC_PCB") (part "XT60PW_F"))
    )
    (comp (ref "L0")
      (value "220uH")
      (footprint "SRR1260")
      (description "L - INDUCTOR - 220uH - 1.6A - 12.5mm")
      (fields (field (name "LCSC PART #") "C169380") (field (name "Comment") "SWRB1207S-221MT"))
      (libsource (lib "JLC_PCB") (part "SWRB1207S-221MT"))
    )
    (comp (ref "L1")
      (value "220uH")
      (footprint "SRR1260")
      (description "L - INDUCTOR - 220uH - 1.6A - 12.5mm")
      (fields (field (name "LCSC PART #") "C169380") (field (name "Comment") "SWRB1207S-221MT"))
      (libsource (lib "JLC_PCB") (part "SWRB1207S-221MT"))
    )
    (comp (ref "L2")
      (value "220uH")
      (footprint "SRR1260")
      (description "L - INDUCTOR - 220uH - 1.6A - 12.5mm")
      (fields (field (name "LCSC PART #") "C169380") (field (name "Comment") "SWRB1207S-221MT"))
      (libsource (lib "JLC_PCB") (part "SWRB1207S-221MT"))
    )
    (comp (ref "L3")
      (value "220uH")
      (footprint "SRR1260")
      (description "L - INDUCTOR - 220uH - 1.6A - 12.5mm")
      (fields (field (name "LCSC PART #") "C169380") (field (name "Comment") "SWRB1207S-221MT"))
      (libsource (lib "JLC_PCB") (part "SWRB1207S-221MT"))
    )
    (comp (ref "L4")
      (value "220uH")
      (footprint "SRR1260")
      (description "L - INDUCTOR - 220uH - 1.6A - 12.5mm")
      (fields (field (name "LCSC PART #") "C169380") (field (name "Comment") "SWRB1207S-221MT"))
      (libsource (lib "JLC_PCB") (part "SWRB1207S-221MT"))
    )
    (comp (ref "L5")
      (value "220uH")
      (footprint "SRR1260")
      (description "L - INDUCTOR - 220uH - 1.6A - 12.5mm")
      (fields (field (name "LCSC PART #") "C169380") (field (name "Comment") "SWRB1207S-221MT"))
      (libsource (lib "JLC_PCB") (part "SWRB1207S-221MT"))
    )
    (comp (ref "L6")
      (value "220uH")
      (footprint "SRR1260")
      (description "L - INDUCTOR - 220uH - 1.6A - 12.5mm")
      (fields (field (name "LCSC PART #") "C169380") (field (name "Comment") "SWRB1207S-221MT"))
      (libsource (lib "JLC_PCB") (part "SWRB1207S-221MT"))
    )
    (comp (ref "L7")
      (value "220uH")
      (footprint "SRR1260")
      (description "L - INDUCTOR - 220uH - 1.6A - 12.5mm")
      (fields (field (name "LCSC PART #") "C169380") (field (name "Comment") "SWRB1207S-221MT"))
      (libsource (lib "JLC_PCB") (part "SWRB1207S-221MT"))
    )
    (comp (ref "L8")
      (value "220uH")
      (footprint "SRR1260")
      (description "L - INDUCTOR - 220uH - 1.6A - 12.5mm")
      (fields (field (name "LCSC PART #") "C169380") (field (name "Comment") "SWRB1207S-221MT"))
      (libsource (lib "JLC_PCB") (part "SWRB1207S-221MT"))
    )
    (comp (ref "L9")
      (value "220uH")
      (footprint "SRR1260")
      (description "L - INDUCTOR - 220uH - 1.6A - 12.5mm")
      (fields (field (name "LCSC PART #") "C169380") (field (name "Comment") "SWRB1207S-221MT"))
      (libsource (lib "JLC_PCB") (part "SWRB1207S-221MT"))
    )
    (comp (ref "NT1")
      (value "0")
      (footprint "NET_TIE")
      (description "R - Net Tie")
      (libsource (lib "JLC_PCB") (part "NET_TIE"))
    )
    (comp (ref "NT2")
      (value "0")
      (footprint "NET_TIE")
      (description "R - Net Tie")
      (libsource (lib "JLC_PCB") (part "NET_TIE"))
    )
    (comp (ref "Q1")
      (value "IRF9540NSTRLPBF")
      (footprint "TO-263-3")
      (description "Q - TRANSISTOR - MOSFET (N) - 250V - 33A - 0.094R")
      (fields (field (name "LCSC PART #") "C33903"))
      (libsource (lib "JLC_PCB") (part "IRF9540NSTRLPBF"))
    )
    (comp (ref "Q2")
      (value "IRF9540NSTRLPBF")
      (footprint "TO-263-3")
      (description "Q - TRANSISTOR - MOSFET (N) - 250V - 33A - 0.094R")
      (fields (field (name "LCSC PART #") "C33903"))
      (libsource (lib "JLC_PCB") (part "IRF9540NSTRLPBF"))
    )
    (comp (ref "Q3")
      (value "IRF9540NSTRLPBF")
      (footprint "TO-263-3")
      (description "Q - TRANSISTOR - MOSFET (N) - 250V - 33A - 0.094R")
      (fields (field (name "LCSC PART #") "C33903"))
      (libsource (lib "JLC_PCB") (part "IRF9540NSTRLPBF"))
    )
    (comp (ref "Q4")
      (value "IRF9540NSTRLPBF")
      (footprint "TO-263-3")
      (description "Q - TRANSISTOR - MOSFET (N) - 250V - 33A - 0.094R")
      (fields (field (name "LCSC PART #") "C33903"))
      (libsource (lib "JLC_PCB") (part "IRF9540NSTRLPBF"))
    )
    (comp (ref "Q_I2C1")
      (value "2N7002")
      (footprint "TO-236AB")
      (description "Q - TRANSISTOR - MOSFET (N) - 60V - 200mW")
      (fields (field (name "LCSC PART #") "C8545"))
      (libsource (lib "JLC_PCB") (part "2N7002"))
    )
    (comp (ref "Q_I2C2")
      (value "2N7002")
      (footprint "TO-236AB")
      (description "Q - TRANSISTOR - MOSFET (N) - 60V - 200mW")
      (fields (field (name "LCSC PART #") "C8545"))
      (libsource (lib "JLC_PCB") (part "2N7002"))
    )
    (comp (ref "Q_LEDA")
      (value "2N7002")
      (footprint "TO-236AB")
      (description "Q - TRANSISTOR - MOSFET (N) - 60V - 200mW")
      (fields (field (name "LCSC PART #") "C8545"))
      (libsource (lib "JLC_PCB") (part "2N7002"))
    )
    (comp (ref "Q_LEDB")
      (value "2N7002")
      (footprint "TO-236AB")
      (description "Q - TRANSISTOR - MOSFET (N) - 60V - 200mW")
      (fields (field (name "LCSC PART #") "C8545"))
      (libsource (lib "JLC_PCB") (part "2N7002"))
    )
    (comp (ref "Q_LEDVSS")
      (value "2N7002")
      (footprint "TO-236AB")
      (description "Q - TRANSISTOR - MOSFET (N) - 60V - 200mW")
      (fields (field (name "LCSC PART #") "C8545"))
      (libsource (lib "JLC_PCB") (part "2N7002"))
    )
    (comp (ref "R1")
      (value "1m")
      (footprint "R_2512")
      (description "R - RESISTOR - SMD - 0.001R - 1% - 2512 - 2W - 50ppm/k")
      (fields (field (name "LCSC PART #") "C349153") (field (name "POWER") "2W"))
      (libsource (lib "JLC_PCB") (part "EWSL2512F1L00S9"))
    )
    (comp (ref "R2")
      (value "1m")
      (footprint "R_2512")
      (description "R - RESISTOR - SMD - 0.001R - 1% - 2512 - 2W - 50ppm/k")
      (fields (field (name "LCSC PART #") "C349153") (field (name "POWER") "2W"))
      (libsource (lib "JLC_PCB") (part "EWSL2512F1L00S9"))
    )
    (comp (ref "R3")
      (value "10k")
      (footprint "R_0402")
      (description "R - RESISTOR - SMD - 10k - 1% - 0402")
      (fields (field (name "LCSC PART #") "C25744") (field (name "Comment") "0402WGF1002TCE"))
      (libsource (lib "JLC_PCB") (part "0402WGF1002TCE"))
    )
    (comp (ref "R4")
      (value "10k")
      (footprint "R_0402")
      (description "R - RESISTOR - SMD - 10k - 1% - 0402")
      (fields (field (name "LCSC PART #") "C25744") (field (name "Comment") "0402WGF1002TCE"))
      (libsource (lib "JLC_PCB") (part "0402WGF1002TCE"))
    )
    (comp (ref "R5")
      (value "33k")
      (footprint "R_0402")
      (description "R - RESISTOR - SMD - 33k - 1% - 0402")
      (fields (field (name "LCSC PART #") "C25779") (field (name "Comment") "0402WGF3302TCE"))
      (libsource (lib "JLC_PCB") (part "0402WGF3302TCE"))
    )
    (comp (ref "R5_a")
      (value "100k")
      (footprint "R_0402")
      (description "R - RESISTOR - SMD - 100k - 1% -  0402")
      (fields (field (name "LCSC PART #") "C25741") (field (name "Comment") "0402WGF1003TCE"))
      (libsource (lib "JLC_PCB") (part "0402WGF1003TCE"))
    )
    (comp (ref "R6")
      (value "1m")
      (footprint "R_2512")
      (description "R - RESISTOR - SMD - 0.001R - 1% - 2512 - 2W - 50ppm/k")
      (fields (field (name "LCSC PART #") "C349153") (field (name "POWER") "2W"))
      (libsource (lib "JLC_PCB") (part "EWSL2512F1L00S9"))
    )
    (comp (ref "R8")
      (value "220R")
      (footprint "R_0402")
      (description "R - RESISTOR - SMD - 220R - 1% - 0402")
      (fields (field (name "LCSC PART #") "C25091") (field (name "Comment") "0402WGF2200TCE"))
      (libsource (lib "JLC_PCB") (part "0402WGF2200TCE"))
    )
    (comp (ref "R8_A")
      (value "220R")
      (footprint "R_0402")
      (description "R - RESISTOR - SMD - 220R - 1% - 0402")
      (fields (field (name "LCSC PART #") "C25091"))
      (libsource (lib "*") (part "0402WGF2200TCE"))
    )
    (comp (ref "R9")
      (value "10k")
      (footprint "R_0402")
      (description "R - RESISTOR - SMD - 10k - 1% - 0402")
      (fields (field (name "LCSC PART #") "C25744") (field (name "Comment") "0402WGF1002TCE"))
      (libsource (lib "JLC_PCB") (part "0402WGF1002TCE"))
    )
    (comp (ref "R10")
      (value "1m")
      (footprint "R_2512")
      (description "R - RESISTOR - SMD - 0.001R - 1% - 2512 - 2W - 50ppm/k")
      (fields (field (name "LCSC PART #") "C349153") (field (name "POWER") "2W"))
      (libsource (lib "JLC_PCB") (part "EWSL2512F1L00S9"))
    )
    (comp (ref "R11")
      (value "10R")
      (footprint "R_1206")
      (description "R - RESISTOR - SMD - 10R - 1% - 1206")
      (fields (field (name "LCSC PART #") "C17903") (field (name "Comment") "1206W4F100JT5E"))
      (libsource (lib "JLC_PCB") (part "1206W4F100JT5E"))
    )
    (comp (ref "R12")
      (value "220R")
      (footprint "R_0402")
      (description "R - RESISTOR - SMD - 220R - 1% - 0402")
      (fields (field (name "LCSC PART #") "C25091") (field (name "Comment") "0402WGF2200TCE"))
      (libsource (lib "JLC_PCB") (part "0402WGF2200TCE"))
    )
    (comp (ref "R12_A")
      (value "220R")
      (footprint "R_0402")
      (description "R - RESISTOR - SMD - 220R - 1% - 0402")
      (fields (field (name "LCSC PART #") "C25091") (field (name "Comment") "0402WGF2200TCE"))
      (libsource (lib "JLC_PCB") (part "0402WGF2200TCE"))
    )
    (comp (ref "R13")
      (value "100k")
      (footprint "R_0603")
      (description "R - RESISTOR - SMD - 100k - 1% -  0603")
      (fields (field (name "LCSC PART #") "C22936") (field (name "Comment") "0603WAF100KT5E"))
      (libsource (lib "JLC_PCB") (part "0603WAF100KT5E"))
    )
    (comp (ref "R14")
      (value "10R")
      (footprint "R_1206")
      (description "R - RESISTOR - SMD - 10R - 1% - 1206")
      (fields (field (name "LCSC PART #") "C17903") (field (name "Comment") "1206W4F100JT5E"))
      (libsource (lib "JLC_PCB") (part "1206W4F100JT5E"))
    )
    (comp (ref "R15")
      (value "3.3k")
      (footprint "R_0402")
      (description "R - RESISTOR - SMD - 3.3k - 1% - 0402")
      (fields (field (name "LCSC PART #") "C25890") (field (name "Comment") "0402WGF3301TCE"))
      (libsource (lib "JLC_PCB") (part "0402WGF3301TCE"))
    )
    (comp (ref "R16")
      (value "0R")
      (footprint "R_0402")
      (description "R - RESISTOR - SMD - 0R - 1% - 0402")
      (fields (field (name "LCSC PART #") "C17168") (field (name "Comment") "0402WGF0000TCE"))
      (libsource (lib "JLC_PCB") (part "0402WGF0000TCE"))
    )
    (comp (ref "R17")
      (value "0R")
      (footprint "R_0402")
      (description "R - RESISTOR - SMD - 0R - 1% - 0402")
      (fields (field (name "LCSC PART #") "C17168") (field (name "Comment") "0402WGF0000TCE"))
      (libsource (lib "JLC_PCB") (part "0402WGF0000TCE"))
    )
    (comp (ref "R18")
      (value "10R")
      (footprint "R_0402")
      (description "R - RESISTOR - SMD - 10R - 1% - 0402")
      (fields (field (name "LCSC PART #") "C25077") (field (name "Comment") "0402WGF100JTCE"))
      (libsource (lib "JLC_PCB") (part "0402WGF100JTCE"))
    )
    (comp (ref "R18_a")
      (value "10R")
      (footprint "R_0402")
      (description "R - RESISTOR - SMD - 10R - 1% - 0402")
      (fields (field (name "LCSC PART #") "C25077") (field (name "Comment") "0402WGF100JTCE"))
      (libsource (lib "JLC_PCB") (part "0402WGF100JTCE"))
    )
    (comp (ref "R19")
      (value "10R")
      (footprint "R_0402")
      (description "R - RESISTOR - SMD - 10R - 1% - 0402")
      (fields (field (name "LCSC PART #") "C25077") (field (name "Comment") "0402WGF100JTCE"))
      (libsource (lib "JLC_PCB") (part "0402WGF100JTCE"))
    )
    (comp (ref "R19_a")
      (value "10R")
      (footprint "R_0402")
      (description "R - RESISTOR - SMD - 10R - 1% - 0402")
      (fields (field (name "LCSC PART #") "C25077") (field (name "Comment") "0402WGF100JTCE"))
      (libsource (lib "JLC_PCB") (part "0402WGF100JTCE"))
    )
    (comp (ref "R20")
      (value "4.7k")
      (footprint "R_0402")
      (description "R - RESISTOR - SMD - 4.7k - 1% - 0402")
      (fields (field (name "LCSC PART #") "C25900") (field (name "Comment") "0402WGF4701TCE"))
      (libsource (lib "JLC_PCB") (part "0402WGF4701TCE"))
    )
    (comp (ref "R21")
      (value "10R")
      (footprint "R_0402")
      (description "R - RESISTOR - SMD - 10R - 1% - 0402")
      (fields (field (name "LCSC PART #") "C25077") (field (name "Comment") "0402WGF100JTCE"))
      (libsource (lib "JLC_PCB") (part "0402WGF100JTCE"))
    )
    (comp (ref "R22")
      (value "10k")
      (footprint "R_0402")
      (description "R - RESISTOR - SMD - 10k - 1% - 0402")
      (fields (field (name "LCSC PART #") "C25744") (field (name "Comment") "0402WGF1002TCE"))
      (libsource (lib "JLC_PCB") (part "0402WGF1002TCE"))
    )
    (comp (ref "R23")
      (value "10k")
      (footprint "R_0402")
      (description "R - RESISTOR - SMD - 10k - 1% - 0402")
      (fields (field (name "LCSC PART #") "C25744") (field (name "Comment") "0402WGF1002TCE"))
      (libsource (lib "JLC_PCB") (part "0402WGF1002TCE"))
    )
    (comp (ref "R24")
      (value "220R")
      (footprint "R_0402")
      (description "R - RESISTOR - SMD - 220R - 1% - 0402")
      (fields (field (name "LCSC PART #") "C25091") (field (name "Comment") "0402WGF2200TCE"))
      (libsource (lib "JLC_PCB") (part "0402WGF2200TCE"))
    )
    (comp (ref "R24_A")
      (value "220R")
      (footprint "R_0402")
      (description "R - RESISTOR - SMD - 220R - 1% - 0402")
      (fields (field (name "LCSC PART #") "C25091") (field (name "Comment") "0402WGF2200TCE"))
      (libsource (lib "JLC_PCB") (part "0402WGF2200TCE"))
    )
    (comp (ref "R24_B")
      (value "220R")
      (footprint "R_0402")
      (description "R - RESISTOR - SMD - 220R - 1% - 0402")
      (fields (field (name "LCSC PART #") "C25091") (field (name "Comment") "0402WGF2200TCE"))
      (libsource (lib "JLC_PCB") (part "0402WGF2200TCE"))
    )
    (comp (ref "R25")
      (value "0R")
      (footprint "R_0402")
      (description "R - RESISTOR - SMD - 0R - 1% - 0402")
      (fields (field (name "LCSC PART #") "C17168") (field (name "Comment") "0402WGF0000TCE"))
      (libsource (lib "JLC_PCB") (part "0402WGF0000TCE"))
    )
    (comp (ref "R26")
      (value "10k")
      (footprint "R_0402")
      (description "R - RESISTOR - SMD - 10k - 1% - 0402")
      (fields (field (name "LCSC PART #") "C25744") (field (name "Comment") "0402WGF1002TCE"))
      (libsource (lib "JLC_PCB") (part "0402WGF1002TCE"))
    )
    (comp (ref "R28")
      (value "33k")
      (footprint "R_0402")
      (description "R - RESISTOR - SMD - 33k - 1% - 0402")
      (fields (field (name "LCSC PART #") "C25779") (field (name "Comment") "0402WGF3302TCE"))
      (libsource (lib "JLC_PCB") (part "0402WGF3302TCE"))
    )
    (comp (ref "R29")
      (value "0R")
      (footprint "R_0402")
      (description "R - RESISTOR - SMD - 0R - 1% - 0402")
      (fields (field (name "LCSC PART #") "C17168") (field (name "Comment") "0402WGF0000TCE"))
      (libsource (lib "JLC_PCB") (part "0402WGF0000TCE"))
    )
    (comp (ref "R30")
      (value "0R")
      (footprint "R_0402")
      (description "R - RESISTOR - SMD - 0R - 1% - 0402")
      (fields (field (name "LCSC PART #") "C17168") (field (name "Comment") "0402WGF0000TCE"))
      (libsource (lib "JLC_PCB") (part "0402WGF0000TCE"))
    )
    (comp (ref "R31")
      (value "0R")
      (footprint "R_0402")
      (description "R - RESISTOR - SMD - 0R - 1% - 0402")
      (fields (field (name "LCSC PART #") "C17168") (field (name "Comment") "0402WGF0000TCE"))
      (libsource (lib "JLC_PCB") (part "0402WGF0000TCE"))
    )
    (comp (ref "R32")
      (value "10R")
      (footprint "R_0402")
      (description "R - RESISTOR - SMD - 10R - 1% - 0402")
      (fields (field (name "LCSC PART #") "C25077") (field (name "Comment") "0402WGF100JTCE"))
      (libsource (lib "JLC_PCB") (part "0402WGF100JTCE"))
    )
    (comp (ref "R32_a")
      (value "10R")
      (footprint "R_0402")
      (description "R - RESISTOR - SMD - 10R - 1% - 0402")
      (fields (field (name "LCSC PART #") "C25077") (field (name "Comment") "0402WGF100JTCE"))
      (libsource (lib "JLC_PCB") (part "0402WGF100JTCE"))
    )
    (comp (ref "R33")
      (value "10R")
      (footprint "R_0402")
      (description "R - RESISTOR - SMD - 10R - 1% - 0402")
      (fields (field (name "LCSC PART #") "C25077") (field (name "Comment") "0402WGF100JTCE"))
      (libsource (lib "JLC_PCB") (part "0402WGF100JTCE"))
    )
    (comp (ref "R33_a")
      (value "10R")
      (footprint "R_0402")
      (description "R - RESISTOR - SMD - 10R - 1% - 0402")
      (fields (field (name "LCSC PART #") "C25077") (field (name "Comment") "0402WGF100JTCE"))
      (libsource (lib "JLC_PCB") (part "0402WGF100JTCE"))
    )
    (comp (ref "R34")
      (value "220R")
      (footprint "R_0402")
      (description "R - RESISTOR - SMD - 220R - 1% - 0402")
      (fields (field (name "LCSC PART #") "C25091") (field (name "Comment") "0402WGF2200TCE"))
      (libsource (lib "JLC_PCB") (part "0402WGF2200TCE"))
    )
    (comp (ref "R35")
      (value "0R")
      (footprint "R_0402")
      (description "R - RESISTOR - SMD - 0R - 1% - 0402")
      (fields (field (name "LCSC PART #") "C17168") (field (name "Comment") "0402WGF0000TCE"))
      (libsource (lib "JLC_PCB") (part "0402WGF0000TCE"))
    )
    (comp (ref "R36")
      (value "10k")
      (footprint "R_0402")
      (description "R - RESISTOR - SMD - 10k - 1% - 0402")
      (fields (field (name "LCSC PART #") "C25744") (field (name "Comment") "0402WGF1002TCE"))
      (libsource (lib "JLC_PCB") (part "0402WGF1002TCE"))
    )
    (comp (ref "R37")
      (value "0R")
      (footprint "R_0402")
      (description "R - RESISTOR - SMD - 0R - 1% - 0402")
      (fields (field (name "LCSC PART #") "C17168") (field (name "Comment") "0402WGF0000TCE"))
      (libsource (lib "JLC_PCB") (part "0402WGF0000TCE"))
    )
    (comp (ref "R38")
      (value "4.7k")
      (footprint "R_0402")
      (description "R - RESISTOR - SMD - 4.7k - 1% - 0402")
      (fields (field (name "LCSC PART #") "C25900") (field (name "Comment") "0402WGF4701TCE"))
      (libsource (lib "JLC_PCB") (part "0402WGF4701TCE"))
    )
    (comp (ref "R39")
      (value "1M")
      (footprint "R_0402")
      (description "R - RESISTOR - SMD - 1M - 1% - 0402")
      (fields (field (name "LCSC PART #") "C26083") (field (name "Comment") "0402WGF1004TCE"))
      (libsource (lib "JLC_PCB") (part "0402WGF1004TCE"))
    )
    (comp (ref "R40")
      (value "1M")
      (footprint "R_0402")
      (description "R - RESISTOR - SMD - 1M - 1% - 0402")
      (fields (field (name "LCSC PART #") "C26083") (field (name "Comment") "0402WGF1004TCE"))
      (libsource (lib "JLC_PCB") (part "0402WGF1004TCE"))
    )
    (comp (ref "R41")
      (value "100k")
      (footprint "R_0402")
      (description "R - RESISTOR - SMD - 100k - 1% -  0402")
      (fields (field (name "LCSC PART #") "C25741") (field (name "Comment") "0402WGF1003TCE"))
      (libsource (lib "JLC_PCB") (part "0402WGF1003TCE"))
    )
    (comp (ref "R42")
      (value "10k")
      (footprint "R_0402")
      (description "R - RESISTOR - SMD - 10k - 1% - 0402")
      (fields (field (name "LCSC PART #") "C25744") (field (name "Comment") "0402WGF1002TCE"))
      (libsource (lib "JLC_PCB") (part "0402WGF1002TCE"))
    )
    (comp (ref "R43")
      (value "10k")
      (footprint "R_0402")
      (description "R - RESISTOR - SMD - 10k - 1% - 0402")
      (fields (field (name "LCSC PART #") "C25744") (field (name "Comment") "0402WGF1002TCE"))
      (libsource (lib "JLC_PCB") (part "0402WGF1002TCE"))
    )
    (comp (ref "R44")
      (value "0R")
      (footprint "R_0402")
      (description "R - RESISTOR - SMD - 0R - 1% - 0402")
      (fields (field (name "LCSC PART #") "C17168") (field (name "Comment") "0402WGF0000TCE"))
      (libsource (lib "JLC_PCB") (part "0402WGF0000TCE"))
    )
    (comp (ref "R45")
      (value "10k")
      (footprint "R_0402")
      (description "R - RESISTOR - SMD - 10k - 1% - 0402")
      (fields (field (name "LCSC PART #") "C25744") (field (name "Comment") "0402WGF1002TCE"))
      (libsource (lib "JLC_PCB") (part "0402WGF1002TCE"))
    )
    (comp (ref "R47")
      (value "10k")
      (footprint "R_0402")
      (description "R - RESISTOR - SMD - 10k - 1% - 0402")
      (fields (field (name "LCSC PART #") "C25744") (field (name "Comment") "0402WGF1002TCE"))
      (libsource (lib "JLC_PCB") (part "0402WGF1002TCE"))
    )
    (comp (ref "R48")
      (value "10k")
      (footprint "R_0402")
      (description "R - RESISTOR - SMD - 10k - 1% - 0402")
      (fields (field (name "LCSC PART #") "C25744") (field (name "Comment") "0402WGF1002TCE"))
      (libsource (lib "JLC_PCB") (part "0402WGF1002TCE"))
    )
    (comp (ref "R51")
      (value "100k")
      (footprint "R_0603")
      (description "R - RESISTOR - SMD - 100k - 1% -  0603")
      (fields (field (name "LCSC PART #") "C22936") (field (name "Comment") "0603WAF100KT5E"))
      (libsource (lib "JLC_PCB") (part "0603WAF100KT5E"))
    )
    (comp (ref "R53")
      (value "4.7k")
      (footprint "R_0402")
      (description "R - RESISTOR - SMD - 4.7k - 1% - 0402")
      (fields (field (name "LCSC PART #") "C25900") (field (name "Comment") "0402WGF4701TCE"))
      (libsource (lib "JLC_PCB") (part "0402WGF4701TCE"))
    )
    (comp (ref "R56")
      (value "47k")
      (footprint "R_0402")
      (description "R - RESISTOR - SMD - 47k - 1% - 0402")
      (fields (field (name "LCSC PART #") "C25792") (field (name "Comment") "0402WGF4702TCE"))
      (libsource (lib "JLC_PCB") (part "0402WGF4702TCE"))
    )
    (comp (ref "R87_a")
      (value "47k")
      (footprint "R_0402")
      (description "R - RESISTOR - SMD - 47k - 1% - 0402")
      (fields (field (name "LCSC PART #") "C25792") (field (name "Comment") "0402WGF4702TCE"))
      (libsource (lib "JLC_PCB") (part "0402WGF4702TCE"))
    )
    (comp (ref "R100")
      (value "1k")
      (footprint "R_0402")
      (description "R - RESISTOR - SMD - 1k - 1% - 0402")
      (fields (field (name "LCSC PART #") "C11702") (field (name "Comment") "0402WGF1001TCE"))
      (libsource (lib "JLC_PCB") (part "0402WGF1001TCE"))
    )
    (comp (ref "R101")
      (value "1k")
      (footprint "R_0402")
      (description "R - RESISTOR - SMD - 1k - 1% - 0402")
      (fields (field (name "LCSC PART #") "C11702") (field (name "Comment") "0402WGF1001TCE"))
      (libsource (lib "JLC_PCB") (part "0402WGF1001TCE"))
    )
    (comp (ref "R102")
      (value "1k")
      (footprint "R_0402")
      (description "R - RESISTOR - SMD - 1k - 1% - 0402")
      (fields (field (name "LCSC PART #") "C11702") (field (name "Comment") "0402WGF1001TCE"))
      (libsource (lib "JLC_PCB") (part "0402WGF1001TCE"))
    )
    (comp (ref "R103")
      (value "1k")
      (footprint "R_0402")
      (description "R - RESISTOR - SMD - 1k - 1% - 0402")
      (fields (field (name "LCSC PART #") "C11702") (field (name "Comment") "0402WGF1001TCE"))
      (libsource (lib "JLC_PCB") (part "0402WGF1001TCE"))
    )
    (comp (ref "R116")
      (value "47k")
      (footprint "R_0402")
      (description "R - RESISTOR - SMD - 47k - 1% - 0402")
      (fields (field (name "LCSC PART #") "C25792") (field (name "Comment") "0402WGF4702TCE"))
      (libsource (lib "JLC_PCB") (part "0402WGF4702TCE"))
    )
    (comp (ref "R121")
      (value "10k")
      (footprint "R_0402")
      (description "R - RESISTOR - SMD - 10k - 1% - 0402")
      (fields (field (name "LCSC PART #") "C25744") (field (name "Comment") "0402WGF1002TCE"))
      (libsource (lib "JLC_PCB") (part "0402WGF1002TCE"))
    )
    (comp (ref "RA1_N")
      (value "0R")
      (footprint "R_0402")
      (description "R - RESISTOR - SMD - 0R - 1% - 0402")
      (fields (field (name "LCSC PART #") "C17168") (field (name "Comment") "0402WGF0000TCE"))
      (libsource (lib "JLC_PCB") (part "0402WGF0000TCE"))
    )
    (comp (ref "RA1_P")
      (value "0R")
      (footprint "R_0402")
      (description "R - RESISTOR - SMD - 0R - 1% - 0402")
      (fields (field (name "LCSC PART #") "C17168") (field (name "Comment") "0402WGF0000TCE"))
      (libsource (lib "JLC_PCB") (part "0402WGF0000TCE"))
    )
    (comp (ref "RA2_N")
      (value "0R")
      (footprint "R_0402")
      (description "R - RESISTOR - SMD - 0R - 1% - 0402")
      (fields (field (name "LCSC PART #") "C17168") (field (name "Comment") "0402WGF0000TCE"))
      (libsource (lib "JLC_PCB") (part "0402WGF0000TCE"))
    )
    (comp (ref "RA2_P")
      (value "0R")
      (footprint "R_0402")
      (description "R - RESISTOR - SMD - 0R - 1% - 0402")
      (fields (field (name "LCSC PART #") "C17168") (field (name "Comment") "0402WGF0000TCE"))
      (libsource (lib "JLC_PCB") (part "0402WGF0000TCE"))
    )
    (comp (ref "RB1_N")
      (value "0R")
      (footprint "R_0402")
      (description "R - RESISTOR - SMD - 0R - 1% - 0402")
      (fields (field (name "LCSC PART #") "C17168") (field (name "Comment") "0402WGF0000TCE"))
      (libsource (lib "JLC_PCB") (part "0402WGF0000TCE"))
    )
    (comp (ref "RB1_P")
      (value "0R")
      (footprint "R_0402")
      (description "R - RESISTOR - SMD - 0R - 1% - 0402")
      (fields (field (name "LCSC PART #") "C17168") (field (name "Comment") "0402WGF0000TCE"))
      (libsource (lib "JLC_PCB") (part "0402WGF0000TCE"))
    )
    (comp (ref "RB2_N")
      (value "0R")
      (footprint "R_0402")
      (description "R - RESISTOR - SMD - 0R - 1% - 0402")
      (fields (field (name "LCSC PART #") "C17168") (field (name "Comment") "0402WGF0000TCE"))
      (libsource (lib "JLC_PCB") (part "0402WGF0000TCE"))
    )
    (comp (ref "RB2_P")
      (value "0R")
      (footprint "R_0402")
      (description "R - RESISTOR - SMD - 0R - 1% - 0402")
      (fields (field (name "LCSC PART #") "C17168") (field (name "Comment") "0402WGF0000TCE"))
      (libsource (lib "JLC_PCB") (part "0402WGF0000TCE"))
    )
    (comp (ref "Ron_a")
      (value "100k")
      (footprint "R_0402")
      (description "R - RESISTOR - SMD - 100k - 1% -  0402")
      (fields (field (name "LCSC PART #") "C25741") (field (name "Comment") "0402WGF1003TCE"))
      (libsource (lib "JLC_PCB") (part "0402WGF1003TCE"))
    )
    (comp (ref "Ron_b")
      (value "100k")
      (footprint "R_0402")
      (description "R - RESISTOR - SMD - 100k - 1% -  0402")
      (fields (field (name "LCSC PART #") "C25741") (field (name "Comment") "0402WGF1003TCE"))
      (libsource (lib "JLC_PCB") (part "0402WGF1003TCE"))
    )
    (comp (ref "Ron_c")
      (value "100k")
      (footprint "R_0402")
      (description "R - RESISTOR - SMD - 100k - 1% -  0402")
      (fields (field (name "LCSC PART #") "C25741") (field (name "Comment") "0402WGF1003TCE"))
      (libsource (lib "JLC_PCB") (part "0402WGF1003TCE"))
    )
    (comp (ref "Ron_d")
      (value "100k")
      (footprint "R_0402")
      (description "R - RESISTOR - SMD - 100k - 1% -  0402")
      (fields (field (name "LCSC PART #") "C25741") (field (name "Comment") "0402WGF1003TCE"))
      (libsource (lib "JLC_PCB") (part "0402WGF1003TCE"))
    )
    (comp (ref "R_1A_a")
      (value "47k")
      (footprint "R_0402")
      (description "R - RESISTOR - SMD - 47k - 1% - 0402")
      (fields (field (name "LCSC PART #") "C25792") (field (name "Comment") "0402WGF4702TCE"))
      (libsource (lib "JLC_PCB") (part "0402WGF4702TCE"))
    )
    (comp (ref "R_1A_b")
      (value "47k")
      (footprint "R_0402")
      (description "R - RESISTOR - SMD - 47k - 1% - 0402")
      (fields (field (name "LCSC PART #") "C25792") (field (name "Comment") "0402WGF4702TCE"))
      (libsource (lib "JLC_PCB") (part "0402WGF4702TCE"))
    )
    (comp (ref "R_1A_c")
      (value "100k")
      (footprint "R_0402")
      (description "R - RESISTOR - SMD - 100k - 1% -  0402")
      (fields (field (name "LCSC PART #") "C25741") (field (name "Comment") "0402WGF1003TCE"))
      (libsource (lib "JLC_PCB") (part "0402WGF1003TCE"))
    )
    (comp (ref "R_1B_a")
      (value "47k")
      (footprint "R_0402")
      (description "R - RESISTOR - SMD - 47k - 1% - 0402")
      (fields (field (name "LCSC PART #") "C25792") (field (name "Comment") "0402WGF4702TCE"))
      (libsource (lib "JLC_PCB") (part "0402WGF4702TCE"))
    )
    (comp (ref "R_1B_b")
      (value "47k")
      (footprint "R_0402")
      (description "R - RESISTOR - SMD - 47k - 1% - 0402")
      (fields (field (name "LCSC PART #") "C25792") (field (name "Comment") "0402WGF4702TCE"))
      (libsource (lib "JLC_PCB") (part "0402WGF4702TCE"))
    )
    (comp (ref "R_1B_c")
      (value "100k")
      (footprint "R_0402")
      (description "R - RESISTOR - SMD - 100k - 1% -  0402")
      (fields (field (name "LCSC PART #") "C25741") (field (name "Comment") "0402WGF1003TCE"))
      (libsource (lib "JLC_PCB") (part "0402WGF1003TCE"))
    )
    (comp (ref "R_LEDA_O")
      (value "0R")
      (footprint "R_0402")
      (description "R - RESISTOR - SMD - 0R - 1% - 0402")
      (fields (field (name "LCSC PART #") "C17168") (field (name "Comment") "0402WGF0000TCE"))
      (libsource (lib "JLC_PCB") (part "0402WGF0000TCE"))
    )
    (comp (ref "R_LEDB_O")
      (value "0R")
      (footprint "R_0402")
      (description "R - RESISTOR - SMD - 0R - 1% - 0402")
      (fields (field (name "LCSC PART #") "C17168") (field (name "Comment") "0402WGF0000TCE"))
      (libsource (lib "JLC_PCB") (part "0402WGF0000TCE"))
    )
    (comp (ref "R_SCL3")
      (value "10k")
      (footprint "R_0402")
      (description "R - RESISTOR - SMD - 10k - 1% - 0402")
      (fields (field (name "LCSC PART #") "C25744") (field (name "Comment") "0402WGF1002TCE"))
      (libsource (lib "JLC_PCB") (part "0402WGF1002TCE"))
    )
    (comp (ref "R_SDA3")
      (value "10k")
      (footprint "R_0402")
      (description "R - RESISTOR - SMD - 10k - 1% - 0402")
      (fields (field (name "LCSC PART #") "C25744") (field (name "Comment") "0402WGF1002TCE"))
      (libsource (lib "JLC_PCB") (part "0402WGF1002TCE"))
    )
    (comp (ref "U1")
      (value "LM5008MMX/NOPB")
      (footprint "SOP65P490X110-8N")
      (description "U - IC - BUCK CONVERTER, ADJUSTABLE, 95V, 350mA")
      (libsource (lib "JLC_PCB") (part "LM5008MMX/NOPB"))
    )
    (comp (ref "U5V")
      (value "L78M05ABDT-TR")
      (footprint "TO-252AA")
      (description "U - IC - 5V Power Regulator")
      (fields (field (name "LCSC PART #") "C58069"))
      (libsource (lib "JLC_PCB") (part "L78M05ABDT-TR"))
    )
    (comp (ref "U7")
      (value "SM72295MAX")
      (footprint "M28B_M")
      (description "Photovoltaic Full Bridge Driver")
      (fields (field (name "MANUFACTURER") "National Semiconductor") (field (name "PARTNUMBER") "SM72295"))
      (libsource (lib "SM_ICs") (part "SM72295"))
    )
    (comp (ref "U8")
      (value "SM72442MTE/NOPB")
      (footprint "MTC28_L")
      (description "Programmable Maximum Power Point Tracking Controller for Photovoltaic Solar Panels")
      (fields (field (name "MANUFACTURER") "National Semiconductor") (field (name "PARTNUMBER") "SM72442"))
      (libsource (lib "SM_ICs") (part "SM72442"))
    )
  )
  (nets
    (net (code "1") (name "+5VDC") (class "Default")
      (node (ref "C32") (pin "2") (pinfunction "2_2") (pintype "passive"))
      (node (ref "C34") (pin "2") (pinfunction "2_2") (pintype "passive"))
      (node (ref "C37") (pin "1") (pinfunction "1_1") (pintype "passive"))
      (node (ref "C38") (pin "2") (pinfunction "2_2") (pintype "passive"))
      (node (ref "C42") (pin "2") (pinfunction "2_2") (pintype "passive"))
      (node (ref "R100") (pin "1") (pinfunction "1_1") (pintype "passive"))
      (node (ref "R101") (pin "1") (pinfunction "1_1") (pintype "passive"))
      (node (ref "R102") (pin "1") (pinfunction "1_1") (pintype "passive"))
      (node (ref "R103") (pin "1") (pinfunction "1_1") (pintype "passive"))
      (node (ref "R17") (pin "2") (pinfunction "2_2") (pintype "passive"))
      (node (ref "R21") (pin "2") (pinfunction "2_2") (pintype "passive"))
      (node (ref "R26") (pin "2") (pinfunction "2_2") (pintype "passive"))
      (node (ref "R28") (pin "2") (pinfunction "2_2") (pintype "passive"))
      (node (ref "R29") (pin "2") (pinfunction "2_2") (pintype "passive"))
      (node (ref "R30") (pin "1") (pinfunction "1_1") (pintype "passive"))
      (node (ref "R31") (pin "2") (pinfunction "2_2") (pintype "passive"))
      (node (ref "R36") (pin "1") (pinfunction "1_1") (pintype "passive"))
      (node (ref "R45") (pin "1") (pinfunction "1_1") (pintype "passive"))
      (node (ref "R47") (pin "2") (pinfunction "2_2") (pintype "passive"))
      (node (ref "R48") (pin "2") (pinfunction "2_2") (pintype "passive"))
      (node (ref "R87_a") (pin "2") (pinfunction "2_2") (pintype "passive"))
      (node (ref "U7") (pin "17") (pinfunction "VDD_17") (pintype "power_in"))
      (node (ref "U8") (pin "3") (pinfunction "VDDD_3") (pintype "power_in"))
    )
    (net (code "2") (name "/1A_GATE") (class "Default")
      (node (ref "D_1A") (pin "2") (pinfunction "A_2") (pintype "passive"))
      (node (ref "D_1A_G") (pin "1") (pinfunction "K_1") (pintype "passive"))
      (node (ref "Q_LEDA") (pin "1") (pinfunction "G_1") (pintype "passive"))
      (node (ref "R_1A_b") (pin "2") (pinfunction "2_2") (pintype "passive"))
      (node (ref "R_1A_c") (pin "2") (pinfunction "2_2") (pintype "passive"))
    )
    (net (code "3") (name "/1B_GATE") (class "Default")
      (node (ref "D_1B") (pin "2") (pinfunction "A_2") (pintype "passive"))
      (node (ref "D_1B_G") (pin "1") (pinfunction "K_1") (pintype "passive"))
      (node (ref "R_1B_b") (pin "2") (pinfunction "2_2") (pintype "passive"))
      (node (ref "R_1B_c") (pin "2") (pinfunction "2_2") (pintype "passive"))
    )
    (net (code "4") (name "/3V3_SCL") (class "Default")
      (node (ref "Q_I2C1") (pin "2") (pinfunction "S_2") (pintype "passive"))
      (node (ref "R_SCL3") (pin "1") (pinfunction "1_1") (pintype "passive"))
    )
    (net (code "5") (name "/3V3_SDA") (class "Default")
      (node (ref "Q_I2C2") (pin "2") (pinfunction "S_2") (pintype "passive"))
      (node (ref "R_SDA3") (pin "1") (pinfunction "1_1") (pintype "passive"))
    )
    (net (code "6") (name "/5V_SCL") (class "Default")
      (node (ref "Q_I2C1") (pin "3") (pinfunction "D_3") (pintype "passive"))
      (node (ref "R48") (pin "1") (pinfunction "1_1") (pintype "passive"))
      (node (ref "U8") (pin "8") (pinfunction "SCL_8") (pintype "input"))
    )
    (net (code "7") (name "/5V_SDA") (class "Default")
      (node (ref "Q_I2C2") (pin "3") (pinfunction "D_3") (pintype "passive"))
      (node (ref "R47") (pin "1") (pinfunction "1_1") (pintype "passive"))
      (node (ref "U8") (pin "9") (pinfunction "SDA_9") (pintype "bidirectional"))
    )
    (net (code "8") (name "/A1_N") (class "Default")
      (node (ref "R12") (pin "1") (pinfunction "1_1") (pintype "passive"))
      (node (ref "RA1_P") (pin "2") (pinfunction "2_2") (pintype "passive"))
      (node (ref "RA2_P") (pin "2") (pinfunction "2_2") (pintype "passive"))
    )
    (net (code "9") (name "/A1_P") (class "Default")
      (node (ref "R8") (pin "1") (pinfunction "1_1") (pintype "passive"))
      (node (ref "RA1_N") (pin "2") (pinfunction "2_2") (pintype "passive"))
      (node (ref "RA2_N") (pin "2") (pinfunction "2_2") (pintype "passive"))
    )
    (net (code "10") (name "/A2_N") (class "Default")
      (node (ref "R24_A") (pin "2") (pinfunction "2_2") (pintype "passive"))
      (node (ref "RB1_N") (pin "2") (pinfunction "2_2") (pintype "passive"))
      (node (ref "RB2_N") (pin "2") (pinfunction "2_2") (pintype "passive"))
    )
    (net (code "11") (name "/A2_P") (class "Default")
      (node (ref "R24_B") (pin "2") (pinfunction "2_2") (pintype "passive"))
      (node (ref "RB1_P") (pin "2") (pinfunction "2_2") (pintype "passive"))
      (node (ref "RB2_P") (pin "2") (pinfunction "2_2") (pintype "passive"))
    )
    (net (code "12") (name "/AIIN") (class "Default")
      (node (ref "C58") (pin "2") (pinfunction "2_2") (pintype "passive"))
      (node (ref "R44") (pin "1") (pinfunction "1_1") (pintype "passive"))
      (node (ref "U8") (pin "19") (pinfunction "AIIN_19") (pintype "input"))
    )
    (net (code "13") (name "/AIOUT") (class "Default")
      (node (ref "C60") (pin "2") (pinfunction "2_2") (pintype "passive"))
      (node (ref "R37") (pin "1") (pinfunction "1_1") (pintype "passive"))
      (node (ref "U8") (pin "21") (pinfunction "AIOUT_21") (pintype "output"))
    )
    (net (code "14") (name "/AVIN") (class "Default")
      (node (ref "C29") (pin "2") (pinfunction "2_2") (pintype "passive"))
      (node (ref "R13") (pin "1") (pinfunction "1_1") (pintype "passive"))
      (node (ref "R20") (pin "1") (pinfunction "1_1") (pintype "passive"))
      (node (ref "U8") (pin "15") (pinfunction "AVIN_15") (pintype "input"))
    )
    (net (code "15") (name "/AVOUT") (class "Default")
      (node (ref "C59") (pin "2") (pinfunction "2_2") (pintype "passive"))
      (node (ref "R51") (pin "1") (pinfunction "1_1") (pintype "passive"))
      (node (ref "R53") (pin "1") (pinfunction "1_1") (pintype "passive"))
      (node (ref "U8") (pin "17") (pinfunction "AVOUT_17") (pintype "output"))
    )
    (net (code "16") (name "/BIN") (class "Default")
      (node (ref "R37") (pin "2") (pinfunction "2_2") (pintype "passive"))
      (node (ref "U7") (pin "4") (pinfunction "BIN_4") (pintype "output"))
    )
    (net (code "17") (name "/BOUT") (class "Default")
      (node (ref "R44") (pin "2") (pinfunction "2_2") (pintype "passive"))
      (node (ref "U7") (pin "11") (pinfunction "BOUT_11") (pintype "output"))
    )
    (net (code "18") (name "/GND_OUT") (class "Default")
      (node (ref "J_OUT") (pin "MINUS") (pinfunction "-_MINUS") (pintype "passive"))
      (node (ref "R6") (pin "2") (pinfunction "2_2") (pintype "passive"))
      (node (ref "RA2_P") (pin "1") (pinfunction "1_1") (pintype "passive"))
    )
    (net (code "19") (name "/HIA") (class "Default")
      (node (ref "U7") (pin "7") (pinfunction "HIA_7") (pintype "input"))
      (node (ref "U8") (pin "26") (pinfunction "HIA_26") (pintype "output"))
    )
    (net (code "20") (name "/HIB") (class "Default")
      (node (ref "U7") (pin "8") (pinfunction "HIB_8") (pintype "input"))
      (node (ref "U8") (pin "25") (pinfunction "HIB_25") (pintype "output"))
    )
    (net (code "21") (name "/HO_A") (class "Default")
      (node (ref "D3") (pin "1") (pinfunction "K_1") (pintype "passive"))
      (node (ref "R18") (pin "1") (pinfunction "1_1") (pintype "passive"))
      (node (ref "R18_a") (pin "1") (pinfunction "1_1") (pintype "passive"))
      (node (ref "U7") (pin "27") (pinfunction "HOA_27") (pintype "output"))
    )
    (net (code "22") (name "/HO_B") (class "Default")
      (node (ref "D4") (pin "1") (pinfunction "K_1") (pintype "passive"))
      (node (ref "R19") (pin "2") (pinfunction "2_2") (pintype "passive"))
      (node (ref "R19_a") (pin "2") (pinfunction "2_2") (pintype "passive"))
      (node (ref "U7") (pin "19") (pinfunction "HOB_19") (pintype "output"))
    )
    (net (code "23") (name "/HS_A") (class "Default")
      (node (ref "C18") (pin "2") (pinfunction "2_2") (pintype "passive"))
      (node (ref "C46") (pin "2") (pinfunction "2_2") (pintype "passive"))
      (node (ref "D12") (pin "1") (pinfunction "K_1") (pintype "passive"))
      (node (ref "D13") (pin "2") (pinfunction "A_2") (pintype "passive"))
      (node (ref "L1") (pin "1") (pinfunction "1_1") (pintype "passive"))
      (node (ref "L2") (pin "1") (pinfunction "1_1") (pintype "passive"))
      (node (ref "L3") (pin "1") (pinfunction "1_1") (pintype "passive"))
      (node (ref "L4") (pin "1") (pinfunction "1_1") (pintype "passive"))
      (node (ref "L5") (pin "1") (pinfunction "1_1") (pintype "passive"))
      (node (ref "L6") (pin "1") (pinfunction "1_1") (pintype "passive"))
      (node (ref "L7") (pin "1") (pinfunction "1_1") (pintype "passive"))
      (node (ref "L8") (pin "1") (pinfunction "1_1") (pintype "passive"))
      (node (ref "L9") (pin "1") (pinfunction "1_1") (pintype "passive"))
      (node (ref "Q1") (pin "3") (pinfunction "S_3") (pintype "passive"))
      (node (ref "Q3") (pin "2") (pinfunction "D_2") (pintype "passive"))
      (node (ref "R4") (pin "1") (pinfunction "1_1") (pintype "passive"))
      (node (ref "U7") (pin "28") (pinfunction "HSA_28") (pintype "passive"))
    )
    (net (code "24") (name "/HS_B") (class "Default")
      (node (ref "C19") (pin "2") (pinfunction "2_2") (pintype "passive"))
      (node (ref "C54") (pin "2") (pinfunction "2_2") (pintype "passive"))
      (node (ref "D7") (pin "2") (pinfunction "A_2") (pintype "passive"))
      (node (ref "D9") (pin "1") (pinfunction "K_1") (pintype "passive"))
      (node (ref "L1") (pin "2") (pinfunction "2_2") (pintype "passive"))
      (node (ref "L2") (pin "2") (pinfunction "2_2") (pintype "passive"))
      (node (ref "L3") (pin "2") (pinfunction "2_2") (pintype "passive"))
      (node (ref "L4") (pin "2") (pinfunction "2_2") (pintype "passive"))
      (node (ref "L5") (pin "2") (pinfunction "2_2") (pintype "passive"))
      (node (ref "L6") (pin "2") (pinfunction "2_2") (pintype "passive"))
      (node (ref "L7") (pin "2") (pinfunction "2_2") (pintype "passive"))
      (node (ref "L8") (pin "2") (pinfunction "2_2") (pintype "passive"))
      (node (ref "L9") (pin "2") (pinfunction "2_2") (pintype "passive"))
      (node (ref "Q2") (pin "3") (pinfunction "S_3") (pintype "passive"))
      (node (ref "Q4") (pin "2") (pinfunction "D_2") (pintype "passive"))
      (node (ref "R3") (pin "2") (pinfunction "2_2") (pintype "passive"))
      (node (ref "U7") (pin "18") (pinfunction "HSB_18") (pintype "passive"))
    )
    (net (code "25") (name "/IIN") (class "Default")
      (node (ref "C61") (pin "2") (pinfunction "2_2") (pintype "passive"))
      (node (ref "R56") (pin "2") (pinfunction "2_2") (pintype "passive"))
      (node (ref "U7") (pin "3") (pinfunction "IIN_3") (pintype "output"))
    )
    (net (code "26") (name "/IOUT") (class "Default")
      (node (ref "C62") (pin "2") (pinfunction "2_2") (pintype "passive"))
      (node (ref "R116") (pin "2") (pinfunction "2_2") (pintype "passive"))
      (node (ref "U7") (pin "12") (pinfunction "IOUT_12") (pintype "output"))
    )
    (net (code "27") (name "/LED_A") (class "Default")
      (node (ref "J1") (pin "9") (pinfunction "9_9") (pintype "passive"))
      (node (ref "J2") (pin "11") (pinfunction "11_11") (pintype "passive"))
      (node (ref "R_LEDB_O") (pin "2") (pinfunction "2_2") (pintype "passive"))
    )
    (net (code "28") (name "/LED_B") (class "Default")
      (node (ref "J1") (pin "11") (pinfunction "11_11") (pintype "passive"))
      (node (ref "J2") (pin "9") (pinfunction "9_9") (pintype "passive"))
      (node (ref "R_LEDA_O") (pin "2") (pinfunction "2_2") (pintype "passive"))
    )
    (net (code "29") (name "/LED_VSS") (class "Default")
      (node (ref "Q_LEDA") (pin "2") (pinfunction "S_2") (pintype "passive"))
      (node (ref "Q_LEDB") (pin "2") (pinfunction "S_2") (pintype "passive"))
      (node (ref "Q_LEDVSS") (pin "3") (pinfunction "D_3") (pintype "passive"))
    )
    (net (code "30") (name "/LIA") (class "Default")
      (node (ref "U7") (pin "6") (pinfunction "LIA_6") (pintype "input"))
      (node (ref "U8") (pin "27") (pinfunction "LIA_27") (pintype "output"))
    )
    (net (code "31") (name "/LIB") (class "Default")
      (node (ref "U7") (pin "9") (pinfunction "LIB_9") (pintype "input"))
      (node (ref "U8") (pin "24") (pinfunction "LIB_24") (pintype "output"))
    )
    (net (code "32") (name "/LO_A") (class "Default")
      (node (ref "D5") (pin "1") (pinfunction "K_1") (pintype "passive"))
      (node (ref "R32") (pin "1") (pinfunction "1_1") (pintype "passive"))
      (node (ref "R32_a") (pin "1") (pinfunction "1_1") (pintype "passive"))
      (node (ref "U7") (pin "24") (pinfunction "LOA_24") (pintype "output"))
    )
    (net (code "33") (name "/LO_B") (class "Default")
      (node (ref "D6") (pin "1") (pinfunction "K_1") (pintype "passive"))
      (node (ref "R33") (pin "2") (pinfunction "2_2") (pintype "passive"))
      (node (ref "R33_a") (pin "2") (pinfunction "2_2") (pintype "passive"))
      (node (ref "U7") (pin "22") (pinfunction "LOB_22") (pintype "output"))
    )
    (net (code "34") (name "/NC4") (class "Default")
      (node (ref "C69") (pin "2") (pinfunction "2_2") (pintype "passive"))
      (node (ref "R87_a") (pin "1") (pinfunction "1_1") (pintype "passive"))
      (node (ref "U8") (pin "23") (pinfunction "NC4_23") (pintype "passive"))
    )
    (net (code "35") (name "/OVS") (class "Default")
      (node (ref "R121") (pin "1") (pinfunction "1_1") (pintype "passive"))
      (node (ref "U7") (pin "16") (pinfunction "OVS_16") (pintype "passive"))
    )
    (net (code "36") (name "/PAN_DET") (class "Default")
      (node (ref "D_1A") (pin "1") (pinfunction "K_1") (pintype "passive"))
      (node (ref "D_1B") (pin "1") (pinfunction "K_1") (pintype "passive"))
      (node (ref "Q_LEDVSS") (pin "1") (pinfunction "G_1") (pintype "passive"))
    )
    (net (code "37") (name "/PM") (class "Default")
      (node (ref "U8") (pin "28") (pinfunction "PM_28") (pintype "input"))
    )
    (net (code "38") (name "/RST") (class "Default")
      (node (ref "U7") (pin "10") (pinfunction "PGD_10") (pintype "open_collector"))
    )
    (net (code "39") (name "/SOL_1A") (class "Default")
      (node (ref "D1_a") (pin "2") (pinfunction "A_2") (pintype "passive"))
      (node (ref "D1_b") (pin "2") (pinfunction "A_2") (pintype "passive"))
      (node (ref "D1_c") (pin "2") (pinfunction "A_2") (pintype "passive"))
      (node (ref "D1_d") (pin "2") (pinfunction "A_2") (pintype "passive"))
      (node (ref "D1_e") (pin "2") (pinfunction "A_2") (pintype "passive"))
      (node (ref "D1_f") (pin "2") (pinfunction "A_2") (pintype "passive"))
      (node (ref "D3_a") (pin "1") (pinfunction "K_1") (pintype "passive"))
      (node (ref "D3_b") (pin "1") (pinfunction "K_1") (pintype "passive"))
      (node (ref "D3_c") (pin "1") (pinfunction "K_1") (pintype "passive"))
      (node (ref "D3_d") (pin "1") (pinfunction "K_1") (pintype "passive"))
      (node (ref "D3_e") (pin "1") (pinfunction "K_1") (pintype "passive"))
      (node (ref "D3_f") (pin "1") (pinfunction "K_1") (pintype "passive"))
      (node (ref "J1") (pin "1") (pinfunction "1_1") (pintype "passive"))
      (node (ref "J1") (pin "2") (pinfunction "2_2") (pintype "passive"))
      (node (ref "J1") (pin "3") (pinfunction "3_3") (pintype "passive"))
      (node (ref "J1") (pin "4") (pinfunction "4_4") (pintype "passive"))
      (node (ref "J1") (pin "5") (pinfunction "5_5") (pintype "passive"))
      (node (ref "J1") (pin "6") (pinfunction "6_6") (pintype "passive"))
      (node (ref "J1") (pin "7") (pinfunction "7_7") (pintype "passive"))
      (node (ref "J1") (pin "8") (pinfunction "8_8") (pintype "passive"))
      (node (ref "J_IN") (pin "PLUS") (pinfunction "+_PLUS") (pintype "passive"))
      (node (ref "R_1A_a") (pin "1") (pinfunction "1_1") (pintype "passive"))
    )
    (net (code "40") (name "/SOL_1B") (class "Default")
      (node (ref "D2_a") (pin "2") (pinfunction "A_2") (pintype "passive"))
      (node (ref "D2_b") (pin "2") (pinfunction "A_2") (pintype "passive"))
      (node (ref "D2_c") (pin "2") (pinfunction "A_2") (pintype "passive"))
      (node (ref "D2_d") (pin "2") (pinfunction "A_2") (pintype "passive"))
      (node (ref "D2_e") (pin "2") (pinfunction "A_2") (pintype "passive"))
      (node (ref "D2_f") (pin "2") (pinfunction "A_2") (pintype "passive"))
      (node (ref "D4_a") (pin "1") (pinfunction "K_1") (pintype "passive"))
      (node (ref "D4_b") (pin "1") (pinfunction "K_1") (pintype "passive"))
      (node (ref "D4_c") (pin "1") (pinfunction "K_1") (pintype "passive"))
      (node (ref "D4_d") (pin "1") (pinfunction "K_1") (pintype "passive"))
      (node (ref "D4_e") (pin "1") (pinfunction "K_1") (pintype "passive"))
      (node (ref "D4_f") (pin "1") (pinfunction "K_1") (pintype "passive"))
      (node (ref "J2") (pin "1") (pinfunction "1_1") (pintype "passive"))
      (node (ref "J2") (pin "2") (pinfunction "2_2") (pintype "passive"))
      (node (ref "J2") (pin "3") (pinfunction "3_3") (pintype "passive"))
      (node (ref "J2") (pin "4") (pinfunction "4_4") (pintype "passive"))
      (node (ref "J2") (pin "5") (pinfunction "5_5") (pintype "passive"))
      (node (ref "J2") (pin "6") (pinfunction "6_6") (pintype "passive"))
      (node (ref "J2") (pin "7") (pinfunction "7_7") (pintype "passive"))
      (node (ref "J2") (pin "8") (pinfunction "8_8") (pintype "passive"))
      (node (ref "J_IN") (pin "MINUS") (pinfunction "-_MINUS") (pintype "passive"))
      (node (ref "R_1B_a") (pin "1") (pinfunction "1_1") (pintype "passive"))
    )
    (net (code "41") (name "/VOUT_N") (class "Default")
      (node (ref "J_OUT") (pin "PLUS") (pinfunction "+_PLUS") (pintype "passive"))
      (node (ref "R10") (pin "2") (pinfunction "2_2") (pintype "passive"))
      (node (ref "RA1_N") (pin "1") (pinfunction "1_1") (pintype "passive"))
    )
    (net (code "42") (name "/nRST") (class "Default")
      (node (ref "C66") (pin "2") (pinfunction "2_2") (pintype "passive"))
      (node (ref "R26") (pin "1") (pinfunction "1_1") (pintype "passive"))
      (node (ref "U8") (pin "1") (pinfunction "RST_1") (pintype "input"))
    )
    (net (code "43") (name "10VDC") (class "Default")
      (node (ref "C23_a") (pin "1") (pinfunction "1_1") (pintype "passive"))
      (node (ref "C23_b") (pin "1") (pinfunction "1_1") (pintype "passive"))
      (node (ref "C23_c") (pin "1") (pinfunction "1_1") (pintype "passive"))
      (node (ref "C23_d") (pin "1") (pinfunction "1_1") (pintype "passive"))
      (node (ref "C23_e") (pin "1") (pinfunction "1_1") (pintype "passive"))
      (node (ref "C23_f") (pin "1") (pinfunction "1_1") (pintype "passive"))
      (node (ref "C23_g") (pin "1") (pinfunction "1_1") (pintype "passive"))
      (node (ref "C24") (pin "2") (pinfunction "2_2") (pintype "passive"))
      (node (ref "C31") (pin "1") (pinfunction "1_1") (pintype "passive"))
      (node (ref "C35") (pin "1") (pinfunction "1_1") (pintype "passive"))
      (node (ref "C40") (pin "2") (pinfunction "2_2") (pintype "passive"))
      (node (ref "L0") (pin "2") (pinfunction "2_2") (pintype "passive"))
      (node (ref "R9") (pin "1") (pinfunction "1_1") (pintype "passive"))
      (node (ref "U5V") (pin "1") (pinfunction "VIN_1") (pintype "input"))
      (node (ref "U7") (pin "21") (pinfunction "VCC1_21") (pintype "power_in"))
      (node (ref "U7") (pin "25") (pinfunction "VCC2_25") (pintype "power_in"))
    )
    (net (code "44") (name "AGND") (class "Default")
      (node (ref "C61") (pin "1") (pinfunction "1_1") (pintype "passive"))
      (node (ref "C62") (pin "1") (pinfunction "1_1") (pintype "passive"))
      (node (ref "NT2") (pin "1") (pinfunction "1_1") (pintype "passive"))
      (node (ref "R116") (pin "1") (pinfunction "1_1") (pintype "passive"))
      (node (ref "R56") (pin "1") (pinfunction "1_1") (pintype "passive"))
      (node (ref "U7") (pin "5") (pinfunction "AGND_5") (pintype "power_in"))
      (node (ref "U8") (pin "13") (pinfunction "VSSA_13") (pintype "power_in"))
    )
    (net (code "45") (name "GND") (class "Default")
      (node (ref "C15") (pin "2") (pinfunction "2_2") (pintype "passive"))
      (node (ref "C21") (pin "1") (pinfunction "1_1") (pintype "passive"))
      (node (ref "C22") (pin "1") (pinfunction "1_1") (pintype "passive"))
      (node (ref "C23_a") (pin "2") (pinfunction "2_2") (pintype "passive"))
      (node (ref "C23_b") (pin "2") (pinfunction "2_2") (pintype "passive"))
      (node (ref "C23_c") (pin "2") (pinfunction "2_2") (pintype "passive"))
      (node (ref "C23_d") (pin "2") (pinfunction "2_2") (pintype "passive"))
      (node (ref "C23_e") (pin "2") (pinfunction "2_2") (pintype "passive"))
      (node (ref "C23_f") (pin "2") (pinfunction "2_2") (pintype "passive"))
      (node (ref "C23_g") (pin "2") (pinfunction "2_2") (pintype "passive"))
      (node (ref "C26") (pin "1") (pinfunction "1_1") (pintype "passive"))
      (node (ref "C29") (pin "1") (pinfunction "1_1") (pintype "passive"))
      (node (ref "C31") (pin "2") (pinfunction "2_2") (pintype "passive"))
      (node (ref "C32") (pin "1") (pinfunction "1_1") (pintype "passive"))
      (node (ref "C33") (pin "2") (pinfunction "2_2") (pintype "passive"))
      (node (ref "C34") (pin "1") (pinfunction "1_1") (pintype "passive"))
      (node (ref "C35") (pin "2") (pinfunction "2_2") (pintype "passive"))
      (node (ref "C37") (pin "2") (pinfunction "2_2") (pintype "passive"))
      (node (ref "C38") (pin "1") (pinfunction "1_1") (pintype "passive"))
      (node (ref "C39") (pin "1") (pinfunction "1_1") (pintype "passive"))
      (node (ref "C40") (pin "1") (pinfunction "1_1") (pintype "passive"))
      (node (ref "C42") (pin "1") (pinfunction "1_1") (pintype "passive"))
      (node (ref "C49") (pin "1") (pinfunction "1_1") (pintype "passive"))
      (node (ref "C50") (pin "1") (pinfunction "1_1") (pintype "passive"))
      (node (ref "C51") (pin "1") (pinfunction "1_1") (pintype "passive"))
      (node (ref "C52") (pin "2") (pinfunction "2_2") (pintype "passive"))
      (node (ref "C58") (pin "1") (pinfunction "1_1") (pintype "passive"))
      (node (ref "C59") (pin "1") (pinfunction "1_1") (pintype "passive"))
      (node (ref "C60") (pin "1") (pinfunction "1_1") (pintype "passive"))
      (node (ref "C64") (pin "1") (pinfunction "1_1") (pintype "passive"))
      (node (ref "C66") (pin "1") (pinfunction "1_1") (pintype "passive"))
      (node (ref "C69") (pin "1") (pinfunction "1_1") (pintype "passive"))
      (node (ref "D2") (pin "2") (pinfunction "A_2") (pintype "passive"))
      (node (ref "D_1A_G") (pin "2") (pinfunction "A_2") (pintype "passive"))
      (node (ref "D_1B_G") (pin "2") (pinfunction "A_2") (pintype "passive"))
      (node (ref "NT1") (pin "2") (pinfunction "2_2") (pintype "passive"))
      (node (ref "NT2") (pin "2") (pinfunction "2_2") (pintype "passive"))
      (node (ref "Q_LEDVSS") (pin "2") (pinfunction "S_2") (pintype "passive"))
      (node (ref "R121") (pin "2") (pinfunction "2_2") (pintype "passive"))
      (node (ref "R15") (pin "1") (pinfunction "1_1") (pintype "passive"))
      (node (ref "R20") (pin "2") (pinfunction "2_2") (pintype "passive"))
      (node (ref "R25") (pin "1") (pinfunction "1_1") (pintype "passive"))
      (node (ref "R35") (pin "1") (pinfunction "1_1") (pintype "passive"))
      (node (ref "R38") (pin "1") (pinfunction "1_1") (pintype "passive"))
      (node (ref "R39") (pin "1") (pinfunction "1_1") (pintype "passive"))
      (node (ref "R40") (pin "1") (pinfunction "1_1") (pintype "passive"))
      (node (ref "R41") (pin "1") (pinfunction "1_1") (pintype "passive"))
      (node (ref "R42") (pin "1") (pinfunction "1_1") (pintype "passive"))
      (node (ref "R43") (pin "1") (pinfunction "1_1") (pintype "passive"))
      (node (ref "R53") (pin "2") (pinfunction "2_2") (pintype "passive"))
      (node (ref "R5_a") (pin "1") (pinfunction "1_1") (pintype "passive"))
      (node (ref "R_1A_c") (pin "1") (pinfunction "1_1") (pintype "passive"))
      (node (ref "R_1B_c") (pin "1") (pinfunction "1_1") (pintype "passive"))
      (node (ref "U1") (pin "4") (pinfunction "RTN_4") (pintype "bidirectional"))
      (node (ref "U5V") (pin "2") (pinfunction "GND_2") (pintype "power_in"))
      (node (ref "U7") (pin "23") (pinfunction "PGND_23") (pintype "power_in"))
      (node (ref "U8") (pin "4") (pinfunction "VSSD_4") (pintype "power_in"))
    )
    (net (code "46") (name "GND_IN") (class "Default")
      (node (ref "D3_a") (pin "2") (pinfunction "A_2") (pintype "passive"))
      (node (ref "D3_b") (pin "2") (pinfunction "A_2") (pintype "passive"))
      (node (ref "D3_c") (pin "2") (pinfunction "A_2") (pintype "passive"))
      (node (ref "D3_d") (pin "2") (pinfunction "A_2") (pintype "passive"))
      (node (ref "D3_e") (pin "2") (pinfunction "A_2") (pintype "passive"))
      (node (ref "D3_f") (pin "2") (pinfunction "A_2") (pintype "passive"))
      (node (ref "D4_a") (pin "2") (pinfunction "A_2") (pintype "passive"))
      (node (ref "D4_b") (pin "2") (pinfunction "A_2") (pintype "passive"))
      (node (ref "D4_c") (pin "2") (pinfunction "A_2") (pintype "passive"))
      (node (ref "D4_d") (pin "2") (pinfunction "A_2") (pintype "passive"))
      (node (ref "D4_e") (pin "2") (pinfunction "A_2") (pintype "passive"))
      (node (ref "D4_f") (pin "2") (pinfunction "A_2") (pintype "passive"))
      (node (ref "D_CLAMP_18") (pin "2") (pinfunction "A_2") (pintype "passive"))
      (node (ref "R2") (pin "2") (pinfunction "2_2") (pintype "passive"))
      (node (ref "RB2_N") (pin "1") (pinfunction "1_1") (pintype "passive"))
    )
    (net (code "47") (name "Net-(D2-K)") (class "Default")
      (node (ref "C17") (pin "2") (pinfunction "2_2") (pintype "passive"))
      (node (ref "D2") (pin "1") (pinfunction "K_1") (pintype "passive"))
      (node (ref "L0") (pin "1") (pinfunction "1_1") (pintype "passive"))
      (node (ref "U1") (pin "1") (pinfunction "SW_1") (pintype "bidirectional"))
    )
    (net (code "48") (name "Net-(D3-A)") (class "Default")
      (node (ref "D3") (pin "2") (pinfunction "A_2") (pintype "passive"))
      (node (ref "Q1") (pin "1") (pinfunction "G_1") (pintype "passive"))
      (node (ref "R18") (pin "2") (pinfunction "2_2") (pintype "passive"))
      (node (ref "R18_a") (pin "2") (pinfunction "2_2") (pintype "passive"))
      (node (ref "R4") (pin "2") (pinfunction "2_2") (pintype "passive"))
    )
    (net (code "49") (name "Net-(D4-A)") (class "Default")
      (node (ref "D4") (pin "2") (pinfunction "A_2") (pintype "passive"))
      (node (ref "Q2") (pin "1") (pinfunction "G_1") (pintype "passive"))
      (node (ref "R19") (pin "1") (pinfunction "1_1") (pintype "passive"))
      (node (ref "R19_a") (pin "1") (pinfunction "1_1") (pintype "passive"))
      (node (ref "R3") (pin "1") (pinfunction "1_1") (pintype "passive"))
    )
    (net (code "50") (name "Net-(D5-A)") (class "Default")
      (node (ref "D5") (pin "2") (pinfunction "A_2") (pintype "passive"))
      (node (ref "Q3") (pin "1") (pinfunction "G_1") (pintype "passive"))
      (node (ref "R22") (pin "2") (pinfunction "2_2") (pintype "passive"))
      (node (ref "R32") (pin "2") (pinfunction "2_2") (pintype "passive"))
      (node (ref "R32_a") (pin "2") (pinfunction "2_2") (pintype "passive"))
    )
    (net (code "51") (name "Net-(D6-A)") (class "Default")
      (node (ref "D6") (pin "2") (pinfunction "A_2") (pintype "passive"))
      (node (ref "Q4") (pin "1") (pinfunction "G_1") (pintype "passive"))
      (node (ref "R23") (pin "1") (pinfunction "1_1") (pintype "passive"))
      (node (ref "R33") (pin "1") (pinfunction "1_1") (pintype "passive"))
      (node (ref "R33_a") (pin "1") (pinfunction "1_1") (pintype "passive"))
    )
    (net (code "52") (name "Net-(D14-A)") (class "Default")
      (node (ref "C19") (pin "1") (pinfunction "1_1") (pintype "passive"))
      (node (ref "D14") (pin "2") (pinfunction "A_2") (pintype "passive"))
      (node (ref "R14") (pin "2") (pinfunction "2_2") (pintype "passive"))
    )
    (net (code "53") (name "Net-(D15-A)") (class "Default")
      (node (ref "C18") (pin "1") (pinfunction "1_1") (pintype "passive"))
      (node (ref "D15") (pin "2") (pinfunction "A_2") (pintype "passive"))
      (node (ref "R11") (pin "2") (pinfunction "2_2") (pintype "passive"))
    )
    (net (code "54") (name "Net-(D_CLAMP_1-A)") (class "Default")
      (node (ref "D_CLAMP_1") (pin "2") (pinfunction "A_2") (pintype "passive"))
      (node (ref "D_CLAMP_2") (pin "1") (pinfunction "K_1") (pintype "passive"))
    )
    (net (code "55") (name "Net-(D_CLAMP_2-A)") (class "Default")
      (node (ref "D_CLAMP_2") (pin "2") (pinfunction "A_2") (pintype "passive"))
      (node (ref "D_CLAMP_3") (pin "1") (pinfunction "K_1") (pintype "passive"))
    )
    (net (code "56") (name "Net-(D_CLAMP_3-A)") (class "Default")
      (node (ref "D_CLAMP_3") (pin "2") (pinfunction "A_2") (pintype "passive"))
      (node (ref "D_CLAMP_4") (pin "1") (pinfunction "K_1") (pintype "passive"))
    )
    (net (code "57") (name "Net-(D_CLAMP_4-A)") (class "Default")
      (node (ref "D_CLAMP_4") (pin "2") (pinfunction "A_2") (pintype "passive"))
      (node (ref "D_CLAMP_5") (pin "1") (pinfunction "K_1") (pintype "passive"))
    )
    (net (code "58") (name "Net-(D_CLAMP_5-A)") (class "Default")
      (node (ref "D_CLAMP_5") (pin "2") (pinfunction "A_2") (pintype "passive"))
      (node (ref "D_CLAMP_6") (pin "1") (pinfunction "K_1") (pintype "passive"))
    )
    (net (code "59") (name "Net-(D_CLAMP_6-A)") (class "Default")
      (node (ref "D_CLAMP_6") (pin "2") (pinfunction "A_2") (pintype "passive"))
      (node (ref "D_CLAMP_7") (pin "1") (pinfunction "K_1") (pintype "passive"))
    )
    (net (code "60") (name "Net-(D_CLAMP_7-A)") (class "Default")
      (node (ref "D_CLAMP_7") (pin "2") (pinfunction "A_2") (pintype "passive"))
      (node (ref "D_CLAMP_8") (pin "1") (pinfunction "K_1") (pintype "passive"))
      (node (ref "R16") (pin "2") (pinfunction "2_2") (pintype "passive"))
    )
    (net (code "61") (name "Net-(D_CLAMP_8-A)") (class "Default")
      (node (ref "D_CLAMP_8") (pin "2") (pinfunction "A_2") (pintype "passive"))
      (node (ref "D_CLAMP_9") (pin "1") (pinfunction "K_1") (pintype "passive"))
    )
    (net (code "62") (name "Net-(D_CLAMP_10-A)") (class "Default")
      (node (ref "D_CLAMP_10") (pin "2") (pinfunction "A_2") (pintype "passive"))
      (node (ref "D_CLAMP_11") (pin "1") (pinfunction "K_1") (pintype "passive"))
    )
    (net (code "63") (name "Net-(D_CLAMP_10-K)") (class "Default")
      (node (ref "D_CLAMP_10") (pin "1") (pinfunction "K_1") (pintype "passive"))
      (node (ref "D_CLAMP_9") (pin "2") (pinfunction "A_2") (pintype "passive"))
      (node (ref "R16") (pin "1") (pinfunction "1_1") (pintype "passive"))
    )
    (net (code "64") (name "Net-(D_CLAMP_11-A)") (class "Default")
      (node (ref "D_CLAMP_11") (pin "2") (pinfunction "A_2") (pintype "passive"))
      (node (ref "D_CLAMP_12") (pin "1") (pinfunction "K_1") (pintype "passive"))
    )
    (net (code "65") (name "Net-(D_CLAMP_12-A)") (class "Default")
      (node (ref "D_CLAMP_12") (pin "2") (pinfunction "A_2") (pintype "passive"))
      (node (ref "D_CLAMP_13") (pin "1") (pinfunction "K_1") (pintype "passive"))
    )
    (net (code "66") (name "Net-(D_CLAMP_13-A)") (class "Default")
      (node (ref "D_CLAMP_13") (pin "2") (pinfunction "A_2") (pintype "passive"))
      (node (ref "D_CLAMP_14") (pin "1") (pinfunction "K_1") (pintype "passive"))
    )
    (net (code "67") (name "Net-(D_CLAMP_14-A)") (class "Default")
      (node (ref "D_CLAMP_14") (pin "2") (pinfunction "A_2") (pintype "passive"))
      (node (ref "D_CLAMP_15") (pin "1") (pinfunction "K_1") (pintype "passive"))
    )
    (net (code "68") (name "Net-(D_CLAMP_15-A)") (class "Default")
      (node (ref "D_CLAMP_15") (pin "2") (pinfunction "A_2") (pintype "passive"))
      (node (ref "D_CLAMP_16") (pin "1") (pinfunction "K_1") (pintype "passive"))
    )
    (net (code "69") (name "Net-(D_CLAMP_16-A)") (class "Default")
      (node (ref "D_CLAMP_16") (pin "2") (pinfunction "A_2") (pintype "passive"))
      (node (ref "D_CLAMP_17") (pin "1") (pinfunction "K_1") (pintype "passive"))
    )
    (net (code "70") (name "Net-(D_CLAMP_17-A)") (class "Default")
      (node (ref "D_CLAMP_17") (pin "2") (pinfunction "A_2") (pintype "passive"))
      (node (ref "D_CLAMP_18") (pin "1") (pinfunction "K_1") (pintype "passive"))
    )
    (net (code "71") (name "Net-(J1-Pad10)") (class "Default")
      (node (ref "J1") (pin "10") (pinfunction "10_10") (pintype "passive"))
      (node (ref "R101") (pin "2") (pinfunction "2_2") (pintype "passive"))
    )
    (net (code "72") (name "Net-(J1-Pad12)") (class "Default")
      (node (ref "J1") (pin "12") (pinfunction "12_12") (pintype "passive"))
      (node (ref "R100") (pin "2") (pinfunction "2_2") (pintype "passive"))
    )
    (net (code "73") (name "Net-(J1-SHIELD-PadS1)") (class "Default")
      (node (ref "J1") (pin "S1") (pinfunction "SHIELD_S1") (pintype "passive"))
      (node (ref "J1") (pin "S2") (pinfunction "SHIELD_S2") (pintype "passive"))
    )
    (net (code "74") (name "Net-(J2-Pad10)") (class "Default")
      (node (ref "J2") (pin "10") (pinfunction "10_10") (pintype "passive"))
      (node (ref "R102") (pin "2") (pinfunction "2_2") (pintype "passive"))
    )
    (net (code "75") (name "Net-(J2-Pad12)") (class "Default")
      (node (ref "J2") (pin "12") (pinfunction "12_12") (pintype "passive"))
      (node (ref "R103") (pin "2") (pinfunction "2_2") (pintype "passive"))
    )
    (net (code "76") (name "Net-(J2-SHIELD-PadS1)") (class "Default")
      (node (ref "J2") (pin "S1") (pinfunction "SHIELD_S1") (pintype "passive"))
      (node (ref "J2") (pin "S2") (pinfunction "SHIELD_S2") (pintype "passive"))
    )
    (net (code "77") (name "Net-(Q_LEDA-D)") (class "Default")
      (node (ref "Q_LEDA") (pin "3") (pinfunction "D_3") (pintype "passive"))
      (node (ref "Q_LEDB") (pin "1") (pinfunction "G_1") (pintype "passive"))
      (node (ref "R_LEDB_O") (pin "1") (pinfunction "1_1") (pintype "passive"))
    )
    (net (code "78") (name "Net-(Q_LEDB-D)") (class "Default")
      (node (ref "Q_LEDB") (pin "3") (pinfunction "D_3") (pintype "passive"))
      (node (ref "R_LEDA_O") (pin "1") (pinfunction "1_1") (pintype "passive"))
    )
    (net (code "79") (name "Net-(R5-Pad1)") (class "Default")
      (node (ref "R5") (pin "1") (pinfunction "1_1") (pintype "passive"))
      (node (ref "R5_a") (pin "2") (pinfunction "2_2") (pintype "passive"))
    )
    (net (code "80") (name "Net-(R8-Pad2)") (class "Default")
      (node (ref "R8") (pin "2") (pinfunction "2_2") (pintype "passive"))
      (node (ref "R8_A") (pin "1") (pinfunction "1_1") (pintype "passive"))
    )
    (net (code "81") (name "Net-(R12-Pad2)") (class "Default")
      (node (ref "R12") (pin "2") (pinfunction "2_2") (pintype "passive"))
      (node (ref "R12_A") (pin "1") (pinfunction "1_1") (pintype "passive"))
    )
    (net (code "82") (name "Net-(R24-Pad2)") (class "Default")
      (node (ref "R24") (pin "2") (pinfunction "2_2") (pintype "passive"))
      (node (ref "R24_A") (pin "1") (pinfunction "1_1") (pintype "passive"))
    )
    (net (code "83") (name "Net-(R24_B-Pad1)") (class "Default")
      (node (ref "R24_B") (pin "1") (pinfunction "1_1") (pintype "passive"))
      (node (ref "R34") (pin "2") (pinfunction "2_2") (pintype "passive"))
    )
    (net (code "84") (name "Net-(R_1A_a-Pad2)") (class "Default")
      (node (ref "R_1A_a") (pin "2") (pinfunction "2_2") (pintype "passive"))
      (node (ref "R_1A_b") (pin "1") (pinfunction "1_1") (pintype "passive"))
    )
    (net (code "85") (name "Net-(R_1B_a-Pad2)") (class "Default")
      (node (ref "R_1B_a") (pin "2") (pinfunction "2_2") (pintype "passive"))
      (node (ref "R_1B_b") (pin "1") (pinfunction "1_1") (pintype "passive"))
    )
    (net (code "86") (name "Net-(Ron_a-Pad1)") (class "Default")
      (node (ref "Ron_a") (pin "1") (pinfunction "1_1") (pintype "passive"))
      (node (ref "Ron_b") (pin "1") (pinfunction "1_1") (pintype "passive"))
    )
    (net (code "87") (name "Net-(Ron_b-Pad2)") (class "Default")
      (node (ref "Ron_b") (pin "2") (pinfunction "2_2") (pintype "passive"))
      (node (ref "Ron_c") (pin "2") (pinfunction "2_2") (pintype "passive"))
      (node (ref "Ron_d") (pin "2") (pinfunction "2_2") (pintype "passive"))
    )
    (net (code "88") (name "Net-(U1-BST)") (class "Default")
      (node (ref "C17") (pin "1") (pinfunction "1_1") (pintype "passive"))
      (node (ref "U1") (pin "2") (pinfunction "BST_2") (pintype "bidirectional"))
    )
    (net (code "89") (name "Net-(U1-FB)") (class "Default")
      (node (ref "C24") (pin "1") (pinfunction "1_1") (pintype "passive"))
      (node (ref "R15") (pin "2") (pinfunction "2_2") (pintype "passive"))
      (node (ref "R9") (pin "2") (pinfunction "2_2") (pintype "passive"))
      (node (ref "U1") (pin "5") (pinfunction "FB_5") (pintype "bidirectional"))
    )
    (net (code "90") (name "Net-(U1-RCL)") (class "Default")
      (node (ref "R5") (pin "2") (pinfunction "2_2") (pintype "passive"))
      (node (ref "U1") (pin "3") (pinfunction "RCL_3") (pintype "input"))
    )
    (net (code "91") (name "Net-(U1-RT{slash}SD)") (class "Default")
      (node (ref "Ron_a") (pin "2") (pinfunction "2_2") (pintype "passive"))
      (node (ref "U1") (pin "6") (pinfunction "RT/SD_6") (pintype "input"))
    )
    (net (code "92") (name "Net-(U1-VCC)") (class "Default")
      (node (ref "C15") (pin "1") (pinfunction "1_1") (pintype "passive"))
      (node (ref "U1") (pin "7") (pinfunction "VCC_7") (pintype "power_in"))
    )
    (net (code "93") (name "Net-(U5V-Vout)") (class "Default")
      (node (ref "R17") (pin "1") (pinfunction "1_1") (pintype "passive"))
      (node (ref "U5V") (pin "3") (pinfunction "Vout_3") (pintype "output"))
    )
    (net (code "94") (name "Net-(U7-HBA)") (class "Default")
      (node (ref "C46") (pin "1") (pinfunction "1_1") (pintype "passive"))
      (node (ref "U7") (pin "26") (pinfunction "HBA_26") (pintype "passive"))
    )
    (net (code "95") (name "Net-(U7-HBB)") (class "Default")
      (node (ref "C54") (pin "1") (pinfunction "1_1") (pintype "passive"))
      (node (ref "U7") (pin "20") (pinfunction "HBB_20") (pintype "passive"))
    )
    (net (code "96") (name "Net-(U7-SDA)") (class "Default")
      (node (ref "R8_A") (pin "2") (pinfunction "2_2") (pintype "passive"))
      (node (ref "U7") (pin "2") (pinfunction "SDA_2") (pintype "input"))
    )
    (net (code "97") (name "Net-(U7-SIA)") (class "Default")
      (node (ref "R12_A") (pin "2") (pinfunction "2_2") (pintype "passive"))
      (node (ref "U7") (pin "1") (pinfunction "SIA_1") (pintype "input"))
    )
    (net (code "98") (name "Net-(U7-SIB)") (class "Default")
      (node (ref "R24") (pin "1") (pinfunction "1_1") (pintype "passive"))
      (node (ref "U7") (pin "14") (pinfunction "SIB_14") (pintype "input"))
    )
    (net (code "99") (name "Net-(U7-SOB)") (class "Default")
      (node (ref "R34") (pin "1") (pinfunction "1_1") (pintype "passive"))
      (node (ref "U7") (pin "13") (pinfunction "SOB_13") (pintype "output"))
    )
    (net (code "100") (name "Net-(U8-A0)") (class "Default")
      (node (ref "C49") (pin "2") (pinfunction "2_2") (pintype "passive"))
      (node (ref "R28") (pin "1") (pinfunction "1_1") (pintype "passive"))
      (node (ref "R38") (pin "2") (pinfunction "2_2") (pintype "passive"))
      (node (ref "U8") (pin "14") (pinfunction "A0_14") (pintype "bidirectional"))
    )
    (net (code "101") (name "Net-(U8-A2)") (class "Default")
      (node (ref "C50") (pin "2") (pinfunction "2_2") (pintype "passive"))
      (node (ref "R29") (pin "1") (pinfunction "1_1") (pintype "passive"))
      (node (ref "R39") (pin "2") (pinfunction "2_2") (pintype "passive"))
      (node (ref "U8") (pin "16") (pinfunction "A2_16") (pintype "bidirectional"))
    )
    (net (code "102") (name "Net-(U8-A4)") (class "Default")
      (node (ref "C51") (pin "2") (pinfunction "2_2") (pintype "passive"))
      (node (ref "R30") (pin "2") (pinfunction "2_2") (pintype "passive"))
      (node (ref "R40") (pin "2") (pinfunction "2_2") (pintype "passive"))
      (node (ref "U8") (pin "18") (pinfunction "A4_18") (pintype "bidirectional"))
    )
    (net (code "103") (name "Net-(U8-A6)") (class "Default")
      (node (ref "C52") (pin "1") (pinfunction "1_1") (pintype "passive"))
      (node (ref "R31") (pin "1") (pinfunction "1_1") (pintype "passive"))
      (node (ref "R41") (pin "2") (pinfunction "2_2") (pintype "passive"))
      (node (ref "U8") (pin "20") (pinfunction "A6_20") (pintype "bidirectional"))
    )
    (net (code "104") (name "Net-(U8-I2C0)") (class "Default")
      (node (ref "R36") (pin "2") (pinfunction "2_2") (pintype "passive"))
      (node (ref "U8") (pin "6") (pinfunction "I2C0_6") (pintype "bidirectional"))
    )
    (net (code "105") (name "Net-(U8-I2C1)") (class "Default")
      (node (ref "R42") (pin "2") (pinfunction "2_2") (pintype "passive"))
      (node (ref "U8") (pin "7") (pinfunction "I2C1_7") (pintype "bidirectional"))
    )
    (net (code "106") (name "Net-(U8-I2C2)") (class "Default")
      (node (ref "R43") (pin "2") (pinfunction "2_2") (pintype "passive"))
      (node (ref "U8") (pin "22") (pinfunction "I2C2_22") (pintype "bidirectional"))
    )
    (net (code "107") (name "Net-(U8-NC1)") (class "Default")
      (node (ref "R35") (pin "2") (pinfunction "2_2") (pintype "passive"))
      (node (ref "U8") (pin "2") (pinfunction "NC1_2") (pintype "passive"))
    )
    (net (code "108") (name "Net-(U8-NC2)") (class "Default")
      (node (ref "R45") (pin "2") (pinfunction "2_2") (pintype "passive"))
      (node (ref "U8") (pin "5") (pinfunction "NC2_5") (pintype "passive"))
    )
    (net (code "109") (name "Net-(U8-NC3)") (class "Default")
      (node (ref "R25") (pin "2") (pinfunction "2_2") (pintype "passive"))
      (node (ref "U8") (pin "10") (pinfunction "NC3_10") (pintype "passive"))
    )
    (net (code "110") (name "Net-(U8-VDDA)") (class "Default")
      (node (ref "C33") (pin "1") (pinfunction "1_1") (pintype "passive"))
      (node (ref "C39") (pin "2") (pinfunction "2_2") (pintype "passive"))
      (node (ref "R21") (pin "1") (pinfunction "1_1") (pintype "passive"))
      (node (ref "U8") (pin "12") (pinfunction "VDDA_12") (pintype "power_in"))
    )
    (net (code "111") (name "PGND") (class "Default")
      (node (ref "C1") (pin "1") (pinfunction "1_1") (pintype "passive"))
      (node (ref "C10") (pin "1") (pinfunction "1_1") (pintype "passive"))
      (node (ref "C11") (pin "1") (pinfunction "1_1") (pintype "passive"))
      (node (ref "C12") (pin "1") (pinfunction "1_1") (pintype "passive"))
      (node (ref "C13") (pin "1") (pinfunction "1_1") (pintype "passive"))
      (node (ref "C16") (pin "1") (pinfunction "1_1") (pintype "passive"))
      (node (ref "C20") (pin "1") (pinfunction "1_1") (pintype "passive"))
      (node (ref "C25") (pin "1") (pinfunction "1_1") (pintype "passive"))
      (node (ref "C27") (pin "1") (pinfunction "1_1") (pintype "passive"))
      (node (ref "C28") (pin "1") (pinfunction "1_1") (pintype "passive"))
      (node (ref "C30") (pin "1") (pinfunction "1_1") (pintype "passive"))
      (node (ref "C36") (pin "1") (pinfunction "1_1") (pintype "passive"))
      (node (ref "C4") (pin "1") (pinfunction "1_1") (pintype "passive"))
      (node (ref "C41") (pin "1") (pinfunction "1_1") (pintype "passive"))
      (node (ref "C44") (pin "1") (pinfunction "1_1") (pintype "passive"))
      (node (ref "C45") (pin "1") (pinfunction "1_1") (pintype "passive"))
      (node (ref "C47") (pin "1") (pinfunction "1_1") (pintype "passive"))
      (node (ref "C5") (pin "1") (pinfunction "1_1") (pintype "passive"))
      (node (ref "C6") (pin "1") (pinfunction "1_1") (pintype "passive"))
      (node (ref "C7") (pin "1") (pinfunction "1_1") (pintype "passive"))
      (node (ref "C70") (pin "1") (pinfunction "1_1") (pintype "passive"))
      (node (ref "C72") (pin "1") (pinfunction "1_1") (pintype "passive"))
      (node (ref "C8") (pin "1") (pinfunction "1_1") (pintype "passive"))
      (node (ref "C9") (pin "1") (pinfunction "1_1") (pintype "passive"))
      (node (ref "D12") (pin "2") (pinfunction "A_2") (pintype "passive"))
      (node (ref "D14") (pin "1") (pinfunction "K_1") (pintype "passive"))
      (node (ref "D15") (pin "1") (pinfunction "K_1") (pintype "passive"))
      (node (ref "D9") (pin "2") (pinfunction "A_2") (pintype "passive"))
      (node (ref "NT1") (pin "1") (pinfunction "1_1") (pintype "passive"))
      (node (ref "Q3") (pin "3") (pinfunction "S_3") (pintype "passive"))
      (node (ref "Q4") (pin "3") (pinfunction "S_3") (pintype "passive"))
      (node (ref "R11") (pin "1") (pinfunction "1_1") (pintype "passive"))
      (node (ref "R14") (pin "1") (pinfunction "1_1") (pintype "passive"))
      (node (ref "R2") (pin "1") (pinfunction "1_1") (pintype "passive"))
      (node (ref "R22") (pin "1") (pinfunction "1_1") (pintype "passive"))
      (node (ref "R23") (pin "2") (pinfunction "2_2") (pintype "passive"))
      (node (ref "R6") (pin "1") (pinfunction "1_1") (pintype "passive"))
      (node (ref "RA2_N") (pin "1") (pinfunction "1_1") (pintype "passive"))
      (node (ref "RB2_P") (pin "1") (pinfunction "1_1") (pintype "passive"))
    )
    (net (code "112") (name "VCC_3V3") (class "Default")
      (node (ref "Q_I2C1") (pin "1") (pinfunction "G_1") (pintype "passive"))
      (node (ref "Q_I2C2") (pin "1") (pinfunction "G_1") (pintype "passive"))
      (node (ref "R_SCL3") (pin "2") (pinfunction "2_2") (pintype "passive"))
      (node (ref "R_SDA3") (pin "2") (pinfunction "2_2") (pintype "passive"))
    )
    (net (code "113") (name "VIN_N") (class "Default")
      (node (ref "C10") (pin "2") (pinfunction "2_2") (pintype "passive"))
      (node (ref "C11") (pin "2") (pinfunction "2_2") (pintype "passive"))
      (node (ref "C12") (pin "2") (pinfunction "2_2") (pintype "passive"))
      (node (ref "C13") (pin "2") (pinfunction "2_2") (pintype "passive"))
      (node (ref "C4") (pin "2") (pinfunction "2_2") (pintype "passive"))
      (node (ref "C5") (pin "2") (pinfunction "2_2") (pintype "passive"))
      (node (ref "C6") (pin "2") (pinfunction "2_2") (pintype "passive"))
      (node (ref "C7") (pin "2") (pinfunction "2_2") (pintype "passive"))
      (node (ref "C70") (pin "2") (pinfunction "2_2") (pintype "passive"))
      (node (ref "C72") (pin "2") (pinfunction "2_2") (pintype "passive"))
      (node (ref "C8") (pin "2") (pinfunction "2_2") (pintype "passive"))
      (node (ref "C9") (pin "2") (pinfunction "2_2") (pintype "passive"))
      (node (ref "D13") (pin "1") (pinfunction "K_1") (pintype "passive"))
      (node (ref "Q1") (pin "2") (pinfunction "D_2") (pintype "passive"))
      (node (ref "R1") (pin "1") (pinfunction "1_1") (pintype "passive"))
      (node (ref "R13") (pin "2") (pinfunction "2_2") (pintype "passive"))
      (node (ref "RB1_P") (pin "1") (pinfunction "1_1") (pintype "passive"))
    )
    (net (code "114") (name "VIN_P") (class "Default")
      (node (ref "C21") (pin "2") (pinfunction "2_2") (pintype "passive"))
      (node (ref "C22") (pin "2") (pinfunction "2_2") (pintype "passive"))
      (node (ref "C26") (pin "2") (pinfunction "2_2") (pintype "passive"))
      (node (ref "C64") (pin "2") (pinfunction "2_2") (pintype "passive"))
      (node (ref "D1_a") (pin "1") (pinfunction "K_1") (pintype "passive"))
      (node (ref "D1_b") (pin "1") (pinfunction "K_1") (pintype "passive"))
      (node (ref "D1_c") (pin "1") (pinfunction "K_1") (pintype "passive"))
      (node (ref "D1_d") (pin "1") (pinfunction "K_1") (pintype "passive"))
      (node (ref "D1_e") (pin "1") (pinfunction "K_1") (pintype "passive"))
      (node (ref "D1_f") (pin "1") (pinfunction "K_1") (pintype "passive"))
      (node (ref "D2_a") (pin "1") (pinfunction "K_1") (pintype "passive"))
      (node (ref "D2_b") (pin "1") (pinfunction "K_1") (pintype "passive"))
      (node (ref "D2_c") (pin "1") (pinfunction "K_1") (pintype "passive"))
      (node (ref "D2_d") (pin "1") (pinfunction "K_1") (pintype "passive"))
      (node (ref "D2_e") (pin "1") (pinfunction "K_1") (pintype "passive"))
      (node (ref "D2_f") (pin "1") (pinfunction "K_1") (pintype "passive"))
      (node (ref "D_CLAMP_1") (pin "1") (pinfunction "K_1") (pintype "passive"))
      (node (ref "R1") (pin "2") (pinfunction "2_2") (pintype "passive"))
      (node (ref "RB1_N") (pin "1") (pinfunction "1_1") (pintype "passive"))
      (node (ref "Ron_c") (pin "1") (pinfunction "1_1") (pintype "passive"))
      (node (ref "Ron_d") (pin "1") (pinfunction "1_1") (pintype "passive"))
      (node (ref "U1") (pin "8") (pinfunction "VIN_8") (pintype "input"))
    )
    (net (code "115") (name "VOUT_P") (class "Default")
      (node (ref "C1") (pin "2") (pinfunction "2_2") (pintype "passive"))
      (node (ref "C16") (pin "2") (pinfunction "2_2") (pintype "passive"))
      (node (ref "C20") (pin "2") (pinfunction "2_2") (pintype "passive"))
      (node (ref "C25") (pin "2") (pinfunction "2_2") (pintype "passive"))
      (node (ref "C27") (pin "2") (pinfunction "2_2") (pintype "passive"))
      (node (ref "C28") (pin "2") (pinfunction "2_2") (pintype "passive"))
      (node (ref "C30") (pin "2") (pinfunction "2_2") (pintype "passive"))
      (node (ref "C36") (pin "2") (pinfunction "2_2") (pintype "passive"))
      (node (ref "C41") (pin "2") (pinfunction "2_2") (pintype "passive"))
      (node (ref "C44") (pin "2") (pinfunction "2_2") (pintype "passive"))
      (node (ref "C45") (pin "2") (pinfunction "2_2") (pintype "passive"))
      (node (ref "C47") (pin "2") (pinfunction "2_2") (pintype "passive"))
      (node (ref "D7") (pin "1") (pinfunction "K_1") (pintype "passive"))
      (node (ref "Q2") (pin "2") (pinfunction "D_2") (pintype "passive"))
      (node (ref "R10") (pin "1") (pinfunction "1_1") (pintype "passive"))
      (node (ref "R51") (pin "2") (pinfunction "2_2") (pintype "passive"))
      (node (ref "RA1_P") (pin "1") (pinfunction "1_1") (pintype "passive"))
    )
    (net (code "116") (name "unconnected-(J_IN-PadM)") (class "Default")
      (node (ref "J_IN") (pin "M") (pinfunction "M_M") (pintype "passive"))
    )
    (net (code "117") (name "unconnected-(J_OUT-PadM)") (class "Default")
      (node (ref "J_OUT") (pin "M") (pinfunction "M_M") (pintype "passive"))
    )
    (net (code "118") (name "unconnected-(U7-OVP-Pad15)") (class "Default")
      (node (ref "U7") (pin "15") (pinfunction "OVP_15") (pintype "passive"))
    )
    (net (code "119") (name "unconnected-(U8-PM_OUT-Pad11)") (class "Default")
      (node (ref "U8") (pin "11") (pinfunction "PM_OUT_11") (pintype "output"))
    )
  )
)
